# PCB-CCU-IRISCTRL.net
KiCad netlist of a schematic drawn in EAGLE
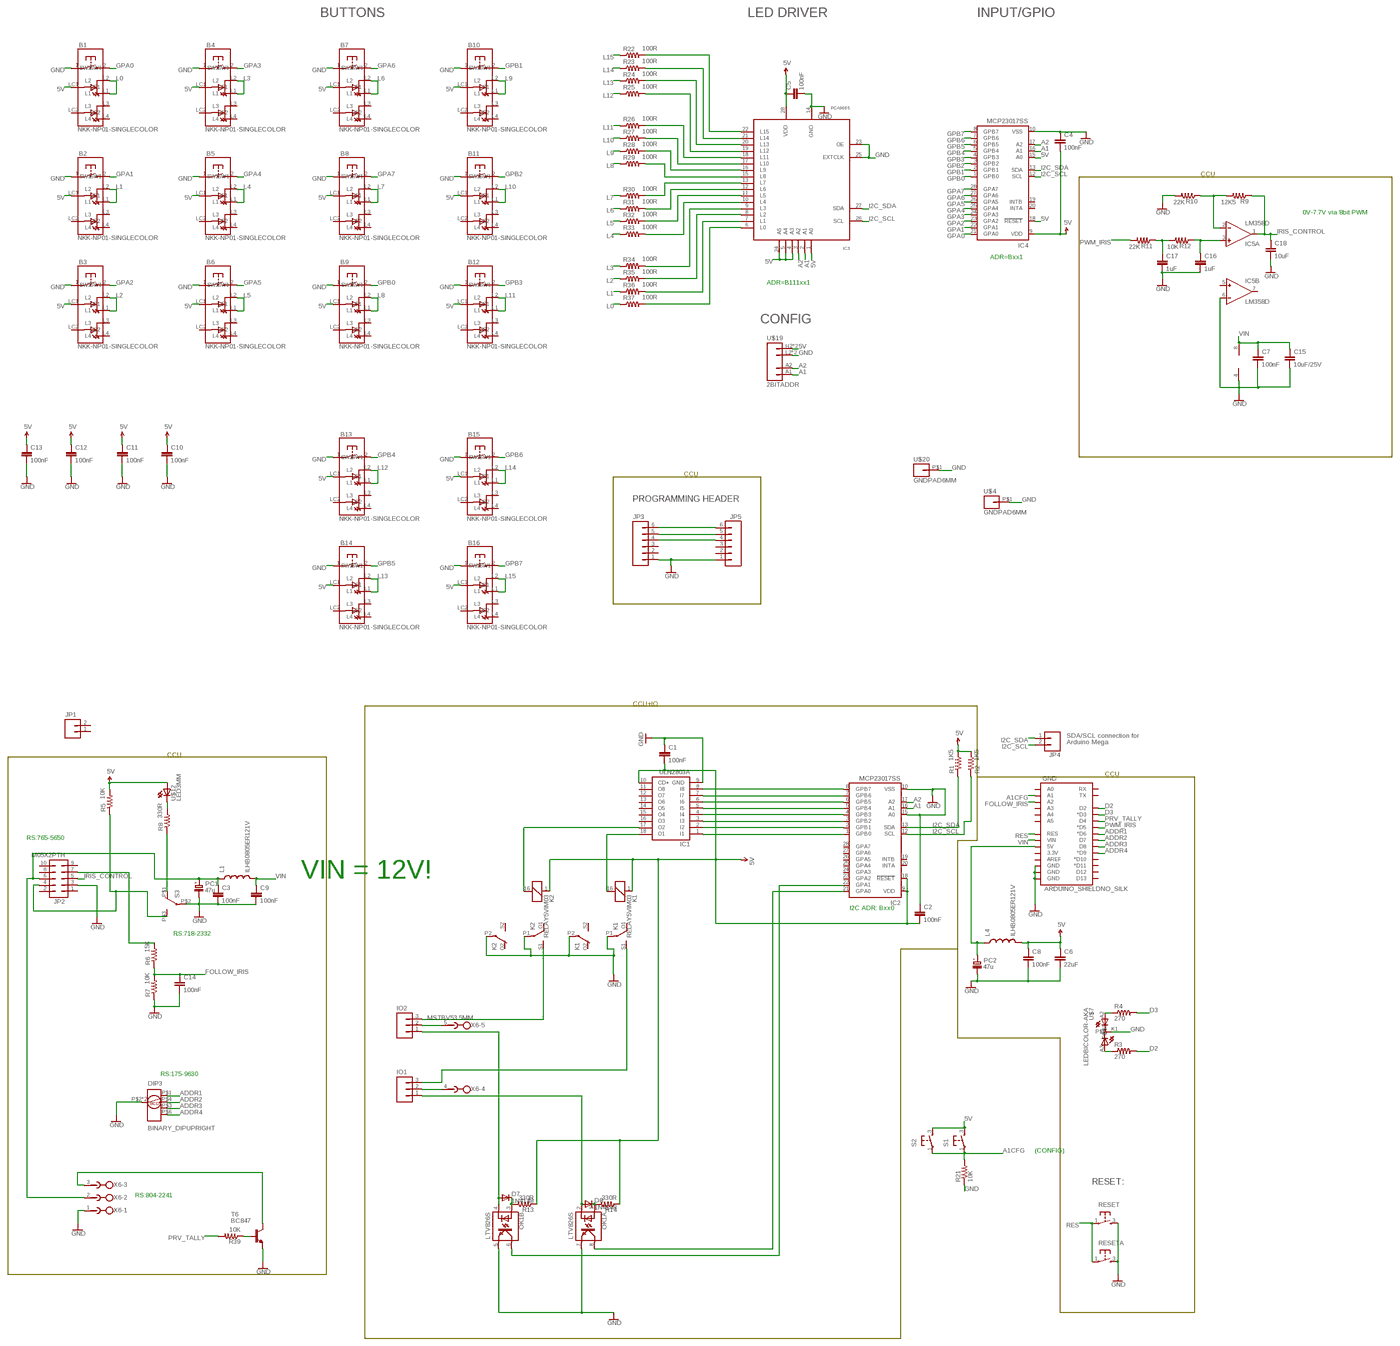
[diagram p0: schematic, sheet 1, overview]
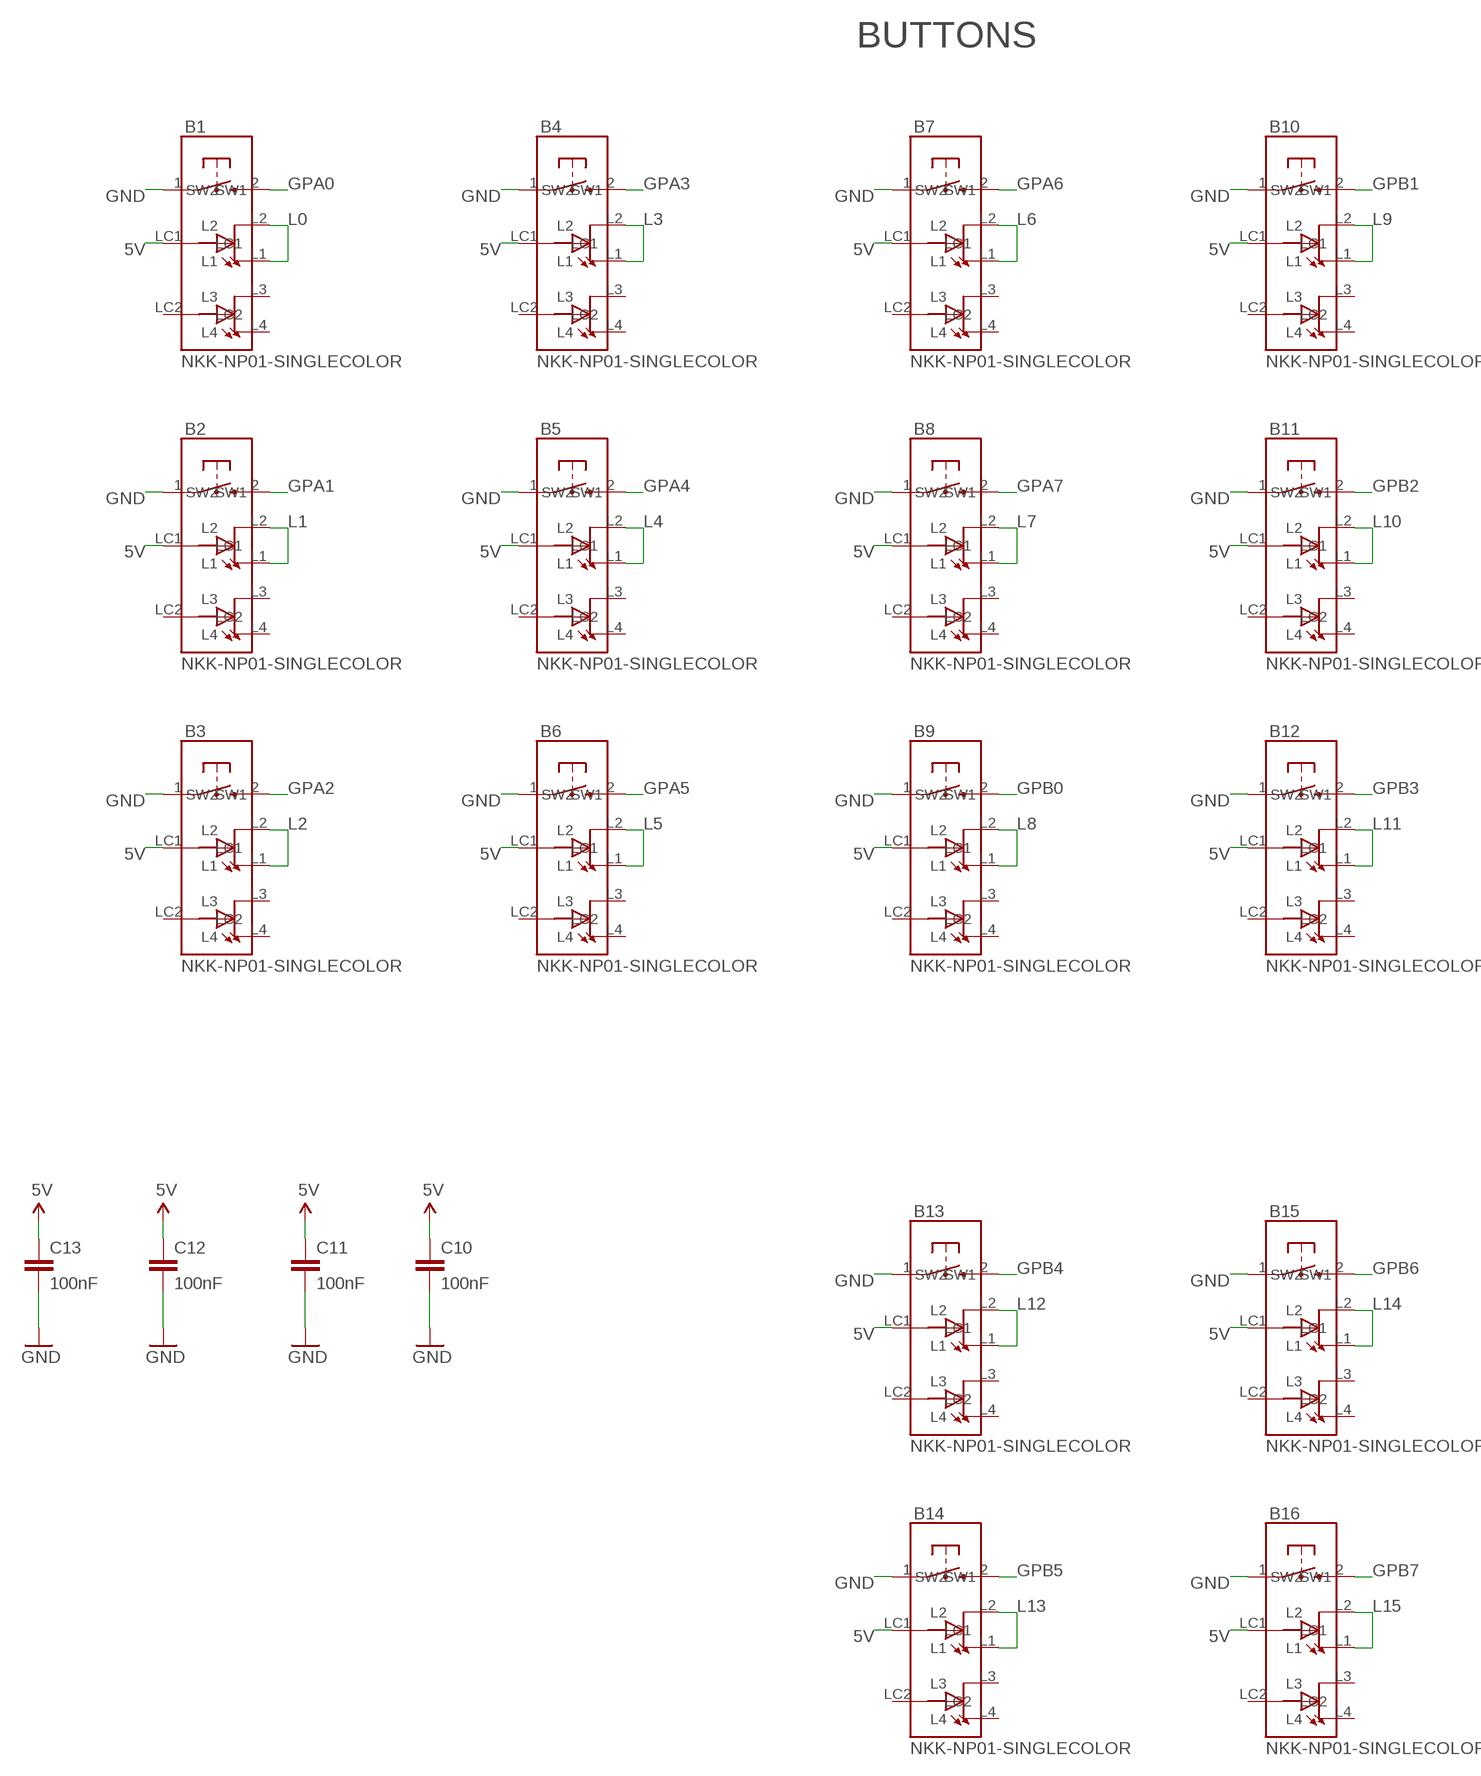
[diagram p1: schematic, sheet 1, part 1 of 4]
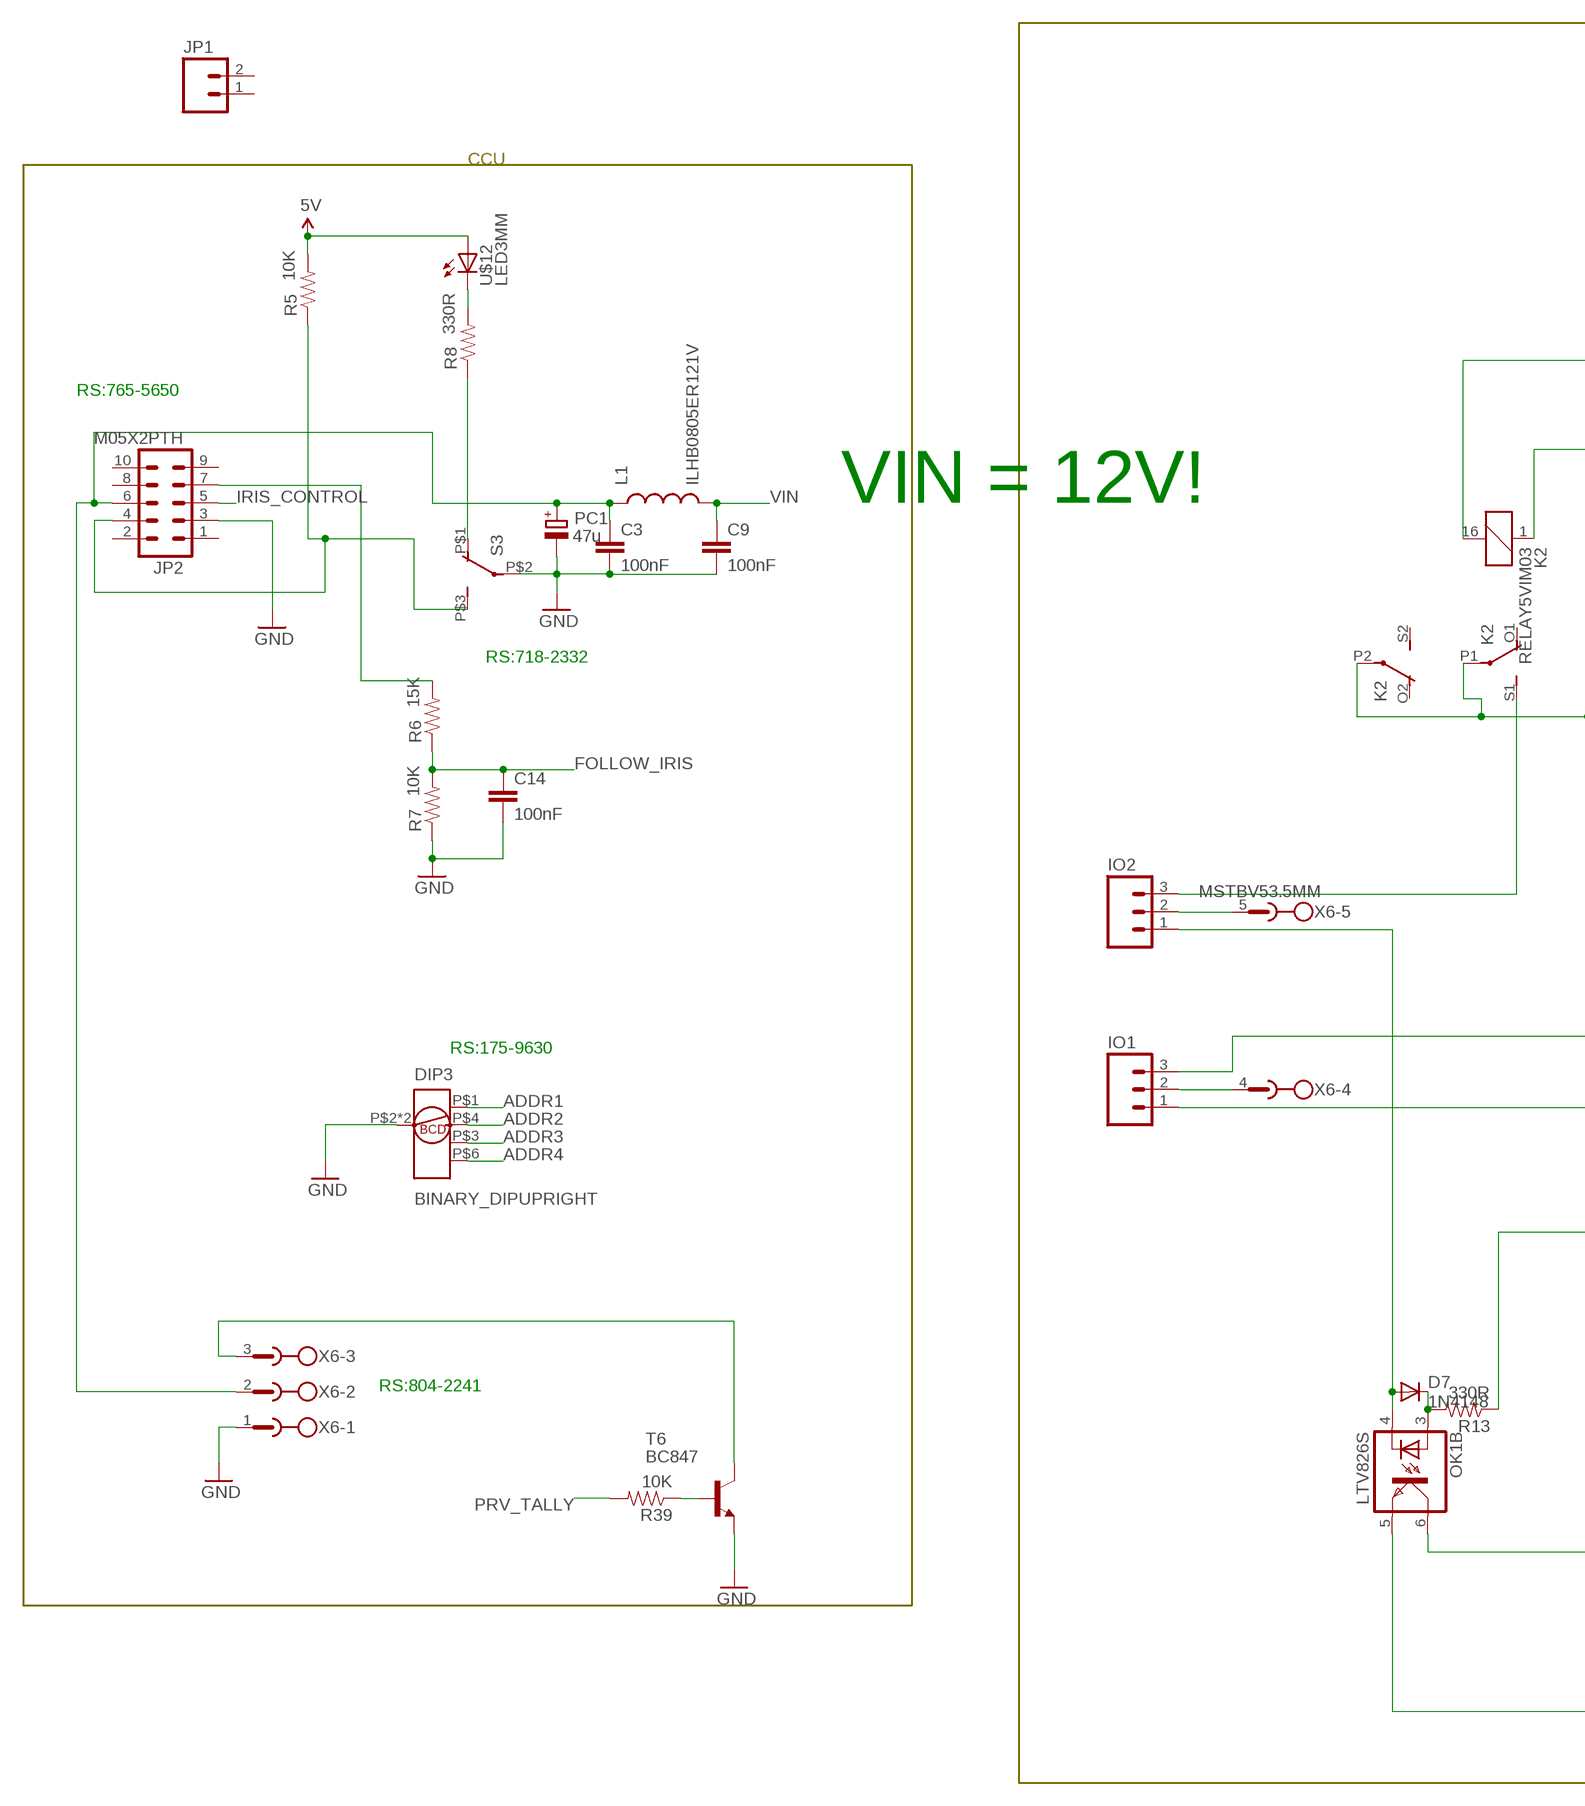
[diagram p2: schematic, sheet 1, part 2 of 4]
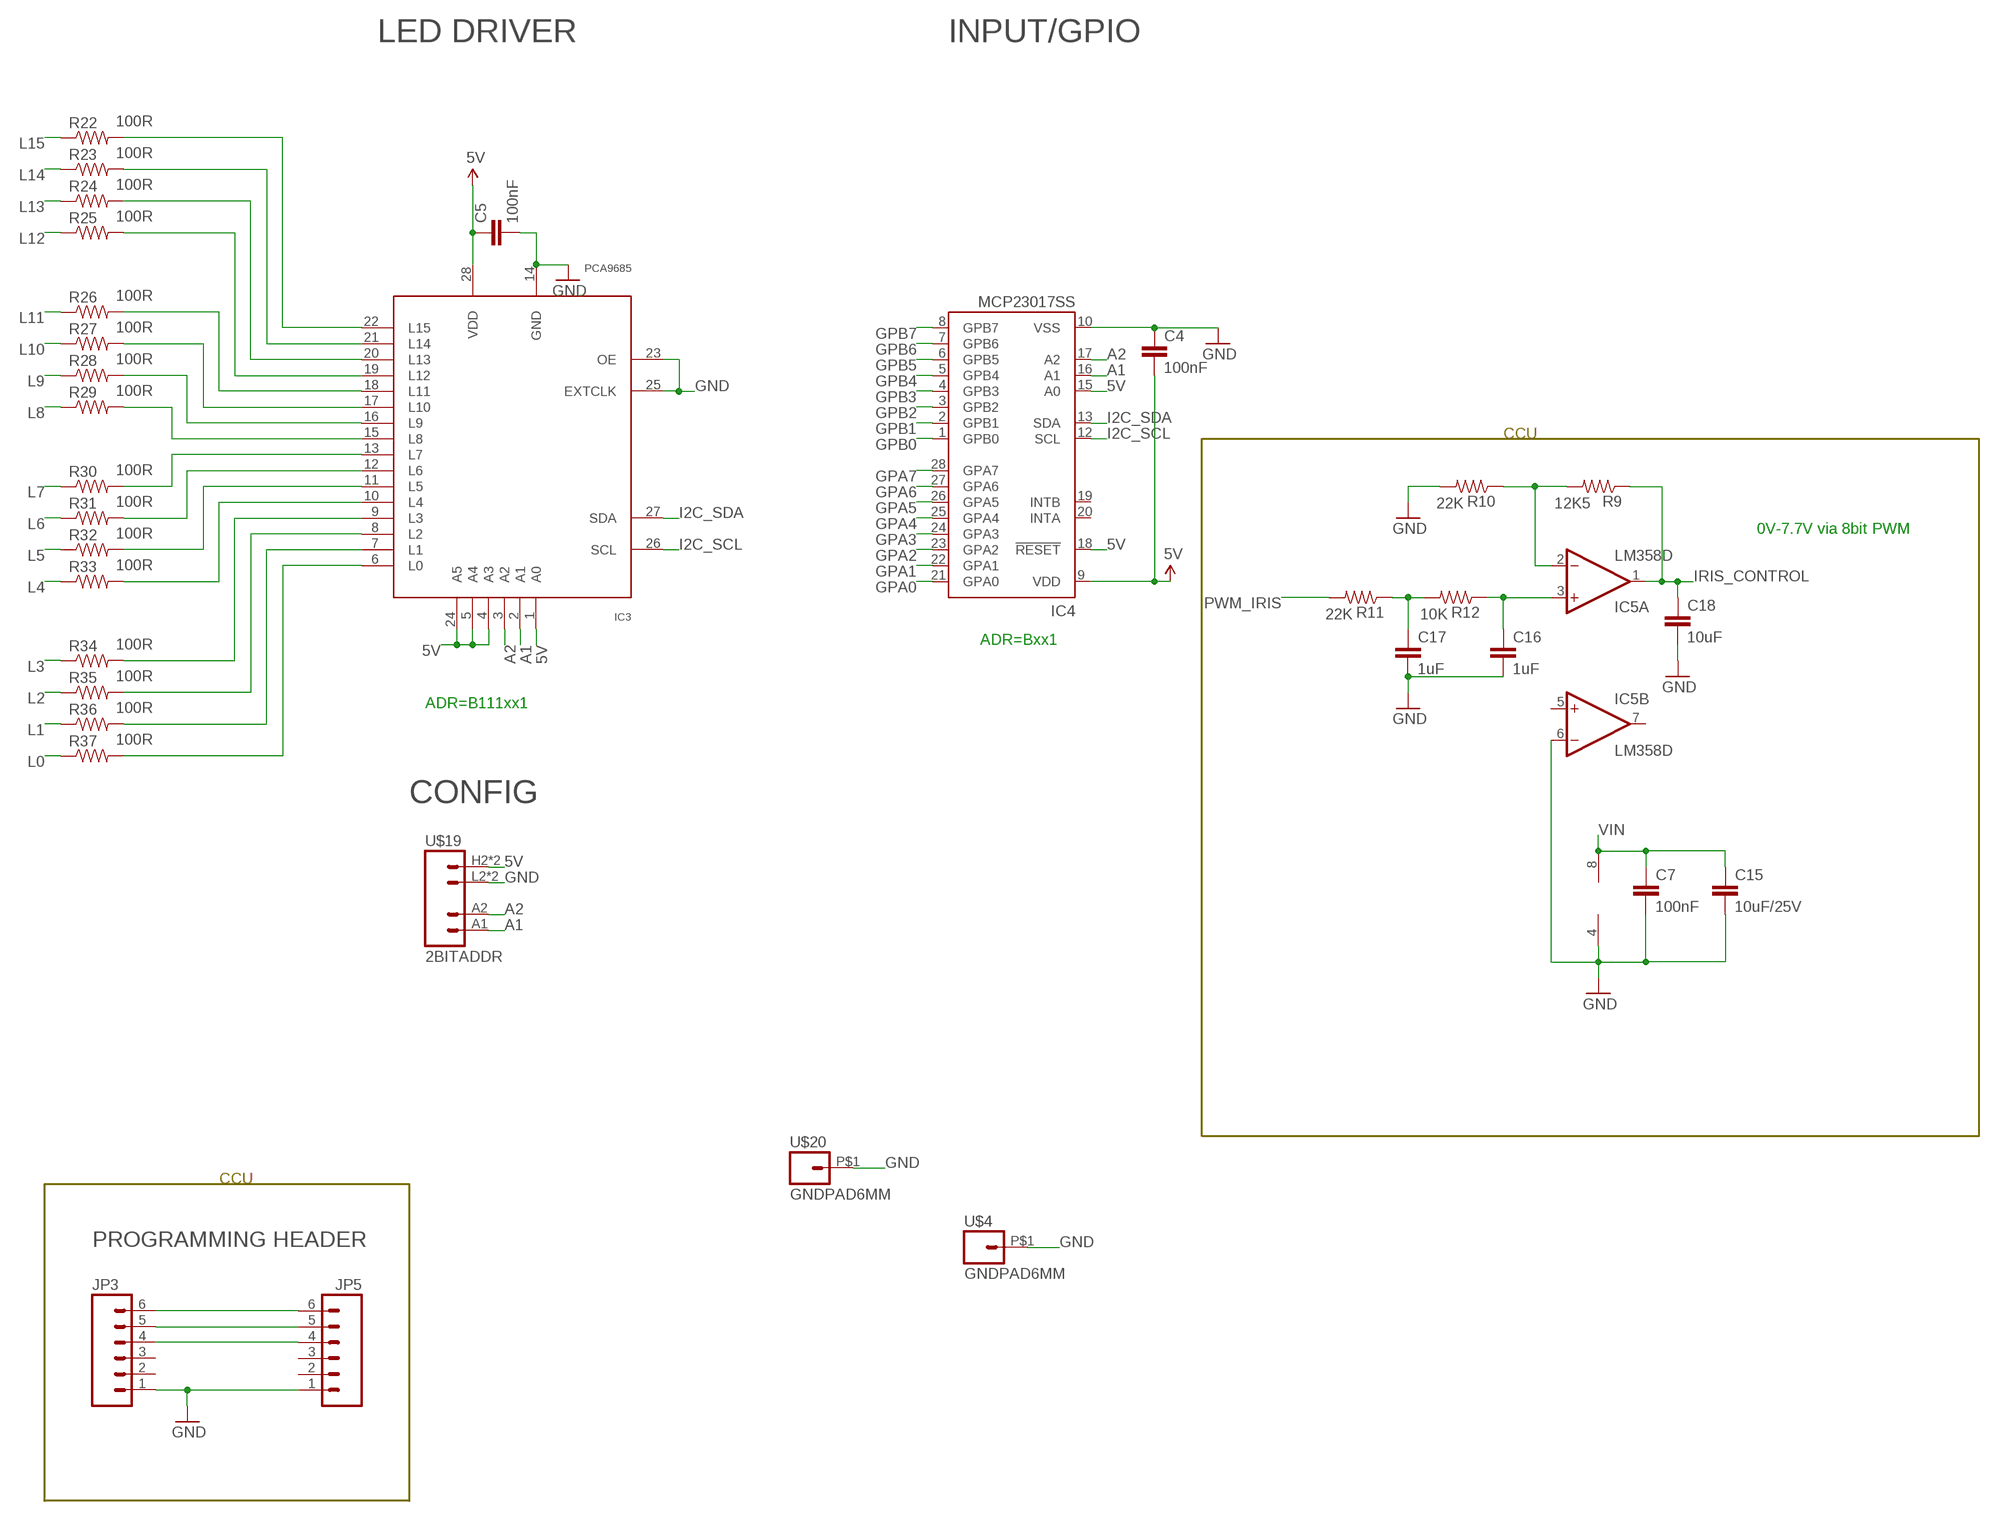
[diagram p3: schematic, sheet 1, part 3 of 4]
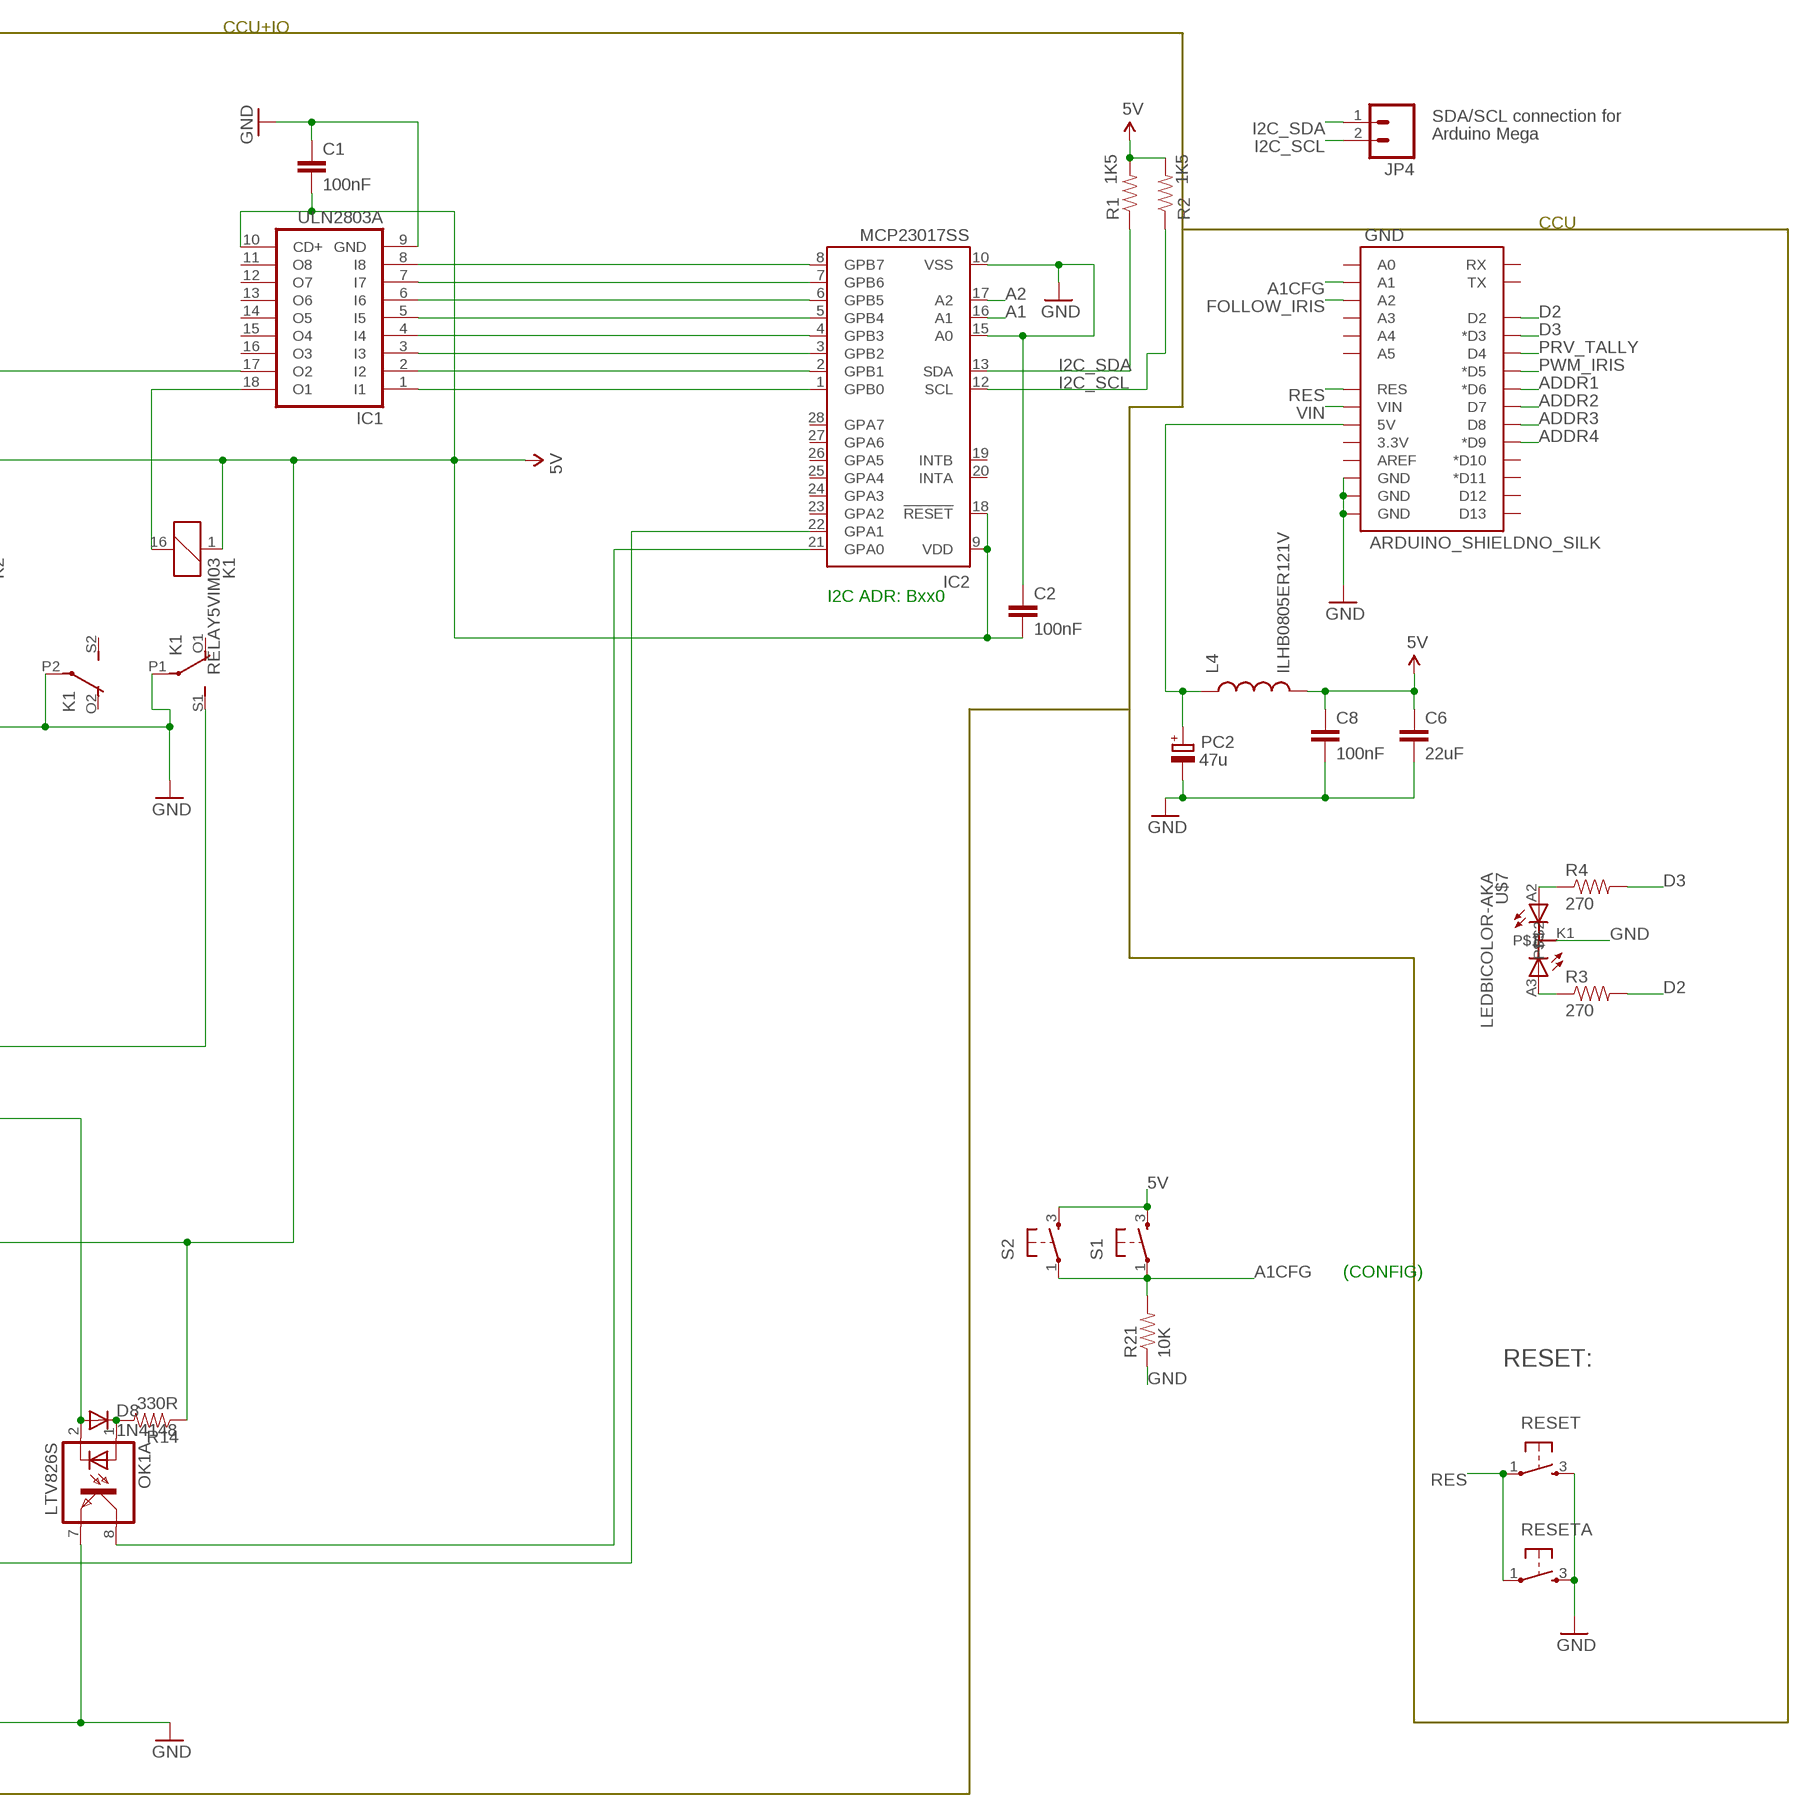
[diagram p4: schematic, sheet 1, part 4 of 4]

(export (version "E")
  (design (tool "Eeschema 10.0.6"))
  (components
    (comp (ref "B1")
      (value "NKK-NP01-SINGLECOLOR")
      (footprint "eagle-import:NKK-NP01")
      (libsource (lib "eagle-import") (part "NKK-NP01-SINGLECOLOR"))
    )
    (comp (ref "B2")
      (value "NKK-NP01-SINGLECOLOR")
      (footprint "eagle-import:NKK-NP01")
      (libsource (lib "eagle-import") (part "NKK-NP01-SINGLECOLOR"))
    )
    (comp (ref "B3")
      (value "NKK-NP01-SINGLECOLOR")
      (footprint "eagle-import:NKK-NP01")
      (libsource (lib "eagle-import") (part "NKK-NP01-SINGLECOLOR"))
    )
    (comp (ref "B4")
      (value "NKK-NP01-SINGLECOLOR")
      (footprint "eagle-import:NKK-NP01")
      (libsource (lib "eagle-import") (part "NKK-NP01-SINGLECOLOR"))
    )
    (comp (ref "B5")
      (value "NKK-NP01-SINGLECOLOR")
      (footprint "eagle-import:NKK-NP01")
      (libsource (lib "eagle-import") (part "NKK-NP01-SINGLECOLOR"))
    )
    (comp (ref "B6")
      (value "NKK-NP01-SINGLECOLOR")
      (footprint "eagle-import:NKK-NP01")
      (libsource (lib "eagle-import") (part "NKK-NP01-SINGLECOLOR"))
    )
    (comp (ref "B7")
      (value "NKK-NP01-SINGLECOLOR")
      (footprint "eagle-import:NKK-NP01")
      (libsource (lib "eagle-import") (part "NKK-NP01-SINGLECOLOR"))
    )
    (comp (ref "B8")
      (value "NKK-NP01-SINGLECOLOR")
      (footprint "eagle-import:NKK-NP01")
      (libsource (lib "eagle-import") (part "NKK-NP01-SINGLECOLOR"))
    )
    (comp (ref "B9")
      (value "NKK-NP01-SINGLECOLOR")
      (footprint "eagle-import:NKK-NP01")
      (libsource (lib "eagle-import") (part "NKK-NP01-SINGLECOLOR"))
    )
    (comp (ref "B10")
      (value "NKK-NP01-SINGLECOLOR")
      (footprint "eagle-import:NKK-NP01")
      (libsource (lib "eagle-import") (part "NKK-NP01-SINGLECOLOR"))
    )
    (comp (ref "B11")
      (value "NKK-NP01-SINGLECOLOR")
      (footprint "eagle-import:NKK-NP01")
      (libsource (lib "eagle-import") (part "NKK-NP01-SINGLECOLOR"))
    )
    (comp (ref "B12")
      (value "NKK-NP01-SINGLECOLOR")
      (footprint "eagle-import:NKK-NP01")
      (libsource (lib "eagle-import") (part "NKK-NP01-SINGLECOLOR"))
    )
    (comp (ref "B13")
      (value "NKK-NP01-SINGLECOLOR")
      (footprint "eagle-import:NKK-NP01")
      (libsource (lib "eagle-import") (part "NKK-NP01-SINGLECOLOR"))
    )
    (comp (ref "B14")
      (value "NKK-NP01-SINGLECOLOR")
      (footprint "eagle-import:NKK-NP01")
      (libsource (lib "eagle-import") (part "NKK-NP01-SINGLECOLOR"))
    )
    (comp (ref "B15")
      (value "NKK-NP01-SINGLECOLOR")
      (footprint "eagle-import:NKK-NP01")
      (libsource (lib "eagle-import") (part "NKK-NP01-SINGLECOLOR"))
    )
    (comp (ref "B16")
      (value "NKK-NP01-SINGLECOLOR")
      (footprint "eagle-import:NKK-NP01")
      (libsource (lib "eagle-import") (part "NKK-NP01-SINGLECOLOR"))
    )
    (comp (ref "C1")
      (value "100nF")
      (footprint "eagle-import:0805")
      (libsource (lib "eagle-import") (part "CAP0805"))
    )
    (comp (ref "C2")
      (value "100nF")
      (footprint "eagle-import:0603-CAP")
      (libsource (lib "eagle-import") (part "CAP0603-CAP"))
    )
    (comp (ref "C3")
      (value "100nF")
      (footprint "eagle-import:0603-CAP")
      (libsource (lib "eagle-import") (part "CAP0603-CAP"))
    )
    (comp (ref "C4")
      (value "100nF")
      (footprint "eagle-import:0603-CAP")
      (libsource (lib "eagle-import") (part "CAP0603-CAP"))
    )
    (comp (ref "C5")
      (value "100nF")
      (footprint "eagle-import:0603-CAP")
      (libsource (lib "eagle-import") (part "CAP0603-CAP"))
    )
    (comp (ref "C6")
      (value "22uF")
      (footprint "eagle-import:0805")
      (libsource (lib "eagle-import") (part "CAP0805"))
    )
    (comp (ref "C7")
      (value "100nF")
      (footprint "eagle-import:0603-CAP")
      (libsource (lib "eagle-import") (part "CAP0603-CAP"))
    )
    (comp (ref "C8")
      (value "100nF")
      (footprint "eagle-import:0603-CAP")
      (libsource (lib "eagle-import") (part "CAP0603-CAP"))
    )
    (comp (ref "C9")
      (value "100nF")
      (footprint "eagle-import:0603-CAP")
      (libsource (lib "eagle-import") (part "CAP0603-CAP"))
    )
    (comp (ref "C10")
      (value "100nF")
      (footprint "eagle-import:0603-CAP")
      (libsource (lib "eagle-import") (part "CAP0603-CAP"))
    )
    (comp (ref "C11")
      (value "100nF")
      (footprint "eagle-import:0603-CAP")
      (libsource (lib "eagle-import") (part "CAP0603-CAP"))
    )
    (comp (ref "C12")
      (value "100nF")
      (footprint "eagle-import:0603-CAP")
      (libsource (lib "eagle-import") (part "CAP0603-CAP"))
    )
    (comp (ref "C13")
      (value "100nF")
      (footprint "eagle-import:0603-CAP")
      (libsource (lib "eagle-import") (part "CAP0603-CAP"))
    )
    (comp (ref "C14")
      (value "100nF")
      (footprint "eagle-import:0603-CAP")
      (libsource (lib "eagle-import") (part "CAP0603-CAP"))
    )
    (comp (ref "C15")
      (value "10uF/25V")
      (footprint "eagle-import:0805")
      (libsource (lib "eagle-import") (part "CAP0805"))
    )
    (comp (ref "C16")
      (value "1uF")
      (footprint "eagle-import:0805")
      (libsource (lib "eagle-import") (part "CAP0805"))
    )
    (comp (ref "C17")
      (value "1uF")
      (footprint "eagle-import:0805")
      (libsource (lib "eagle-import") (part "CAP0805"))
    )
    (comp (ref "C18")
      (value "10uF")
      (footprint "eagle-import:0805")
      (libsource (lib "eagle-import") (part "CAP0805"))
    )
    (comp (ref "D7")
      (value "1N4148")
      (footprint "eagle-import:SOD-323")
      (libsource (lib "eagle-import") (part "DIODESOD"))
    )
    (comp (ref "D8")
      (value "1N4148")
      (footprint "eagle-import:SOD-323")
      (libsource (lib "eagle-import") (part "DIODESOD"))
    )
    (comp (ref "DIP3")
      (value "BINARY_DIPUPRIGHT")
      (footprint "eagle-import:P65SMT_UPRIGHT_TH")
      (libsource (lib "eagle-import") (part "BINARY_DIPUPRIGHT"))
    )
    (comp (ref "GND")
      (value "ARDUINO_SHIELDNO_SILK")
      (footprint "eagle-import:DUEMILANOVE_VIAS")
      (libsource (lib "eagle-import") (part "ARDUINO_SHIELDNO_SILK"))
    )
    (comp (ref "IC1")
      (value "ULN2803A")
      (footprint "eagle-import:SO18W")
      (libsource (lib "eagle-import") (part "ULN2803ASO18W"))
    )
    (comp (ref "IC2")
      (value "MCP23017SS")
      (footprint "eagle-import:SSOP28")
      (fields (field (name "MF") "MICROCHIP") (field (name "MPN") "MCP23017-E/SS"))
      (libsource (lib "eagle-import") (part "MCP23017SS"))
    )
    (comp (ref "IC3")
      (value "PCA9685")
      (footprint "eagle-import:TSSOP28")
      (libsource (lib "eagle-import") (part "PCA9685"))
    )
    (comp (ref "IC4")
      (value "MCP23017SS")
      (footprint "eagle-import:SSOP28")
      (fields
        (field (name "MF") "MICROCHIP")
        (field (name "MPN") "MCP23017-E/SS")
        (field (name "MPN_1") "MCP23017-E/SS")
        (field (name "OC_FARNELL") "1467674")
        (field (name "OC_NEWARK") "31K2960")
      )
      (libsource (lib "eagle-import") (part "MCP23017SS"))
    )
    (comp (ref "IC5")
      (value "LM358D")
      (footprint "eagle-import:SO08")
      (libsource (lib "eagle-import") (part "LM358D"))
    )
    (comp (ref "IO1")
      (value "M03LOCK")
      (footprint "eagle-import:1X03_LOCK")
      (libsource (lib "eagle-import") (part "M03LOCK"))
    )
    (comp (ref "IO2")
      (value "M03LOCK")
      (footprint "eagle-import:1X03_LOCK")
      (libsource (lib "eagle-import") (part "M03LOCK"))
    )
    (comp (ref "JP1")
      (value "M02PTH")
      (footprint "eagle-import:1X02")
      (libsource (lib "eagle-import") (part "M02PTH"))
    )
    (comp (ref "JP2")
      (value "M05X2PTH")
      (footprint "eagle-import:AVR_ICSP")
      (libsource (lib "eagle-import") (part "M05X2PTH"))
    )
    (comp (ref "JP3")
      (value "M06POLAR")
      (footprint "eagle-import:MOLEX-1X6")
      (libsource (lib "eagle-import") (part "M06POLAR"))
    )
    (comp (ref "JP4")
      (value "M02PTH")
      (footprint "eagle-import:1X02")
      (libsource (lib "eagle-import") (part "M02PTH"))
    )
    (comp (ref "JP5")
      (value "M06POLAR")
      (footprint "eagle-import:MOLEX-1X6")
      (libsource (lib "eagle-import") (part "M06POLAR"))
    )
    (comp (ref "K1")
      (value "RELAY5VIM03")
      (footprint "eagle-import:DS2Y")
      (libsource (lib "eagle-import") (part "RELAY5VIM03"))
    )
    (comp (ref "K2")
      (value "RELAY5VIM03")
      (footprint "eagle-import:DS2Y")
      (libsource (lib "eagle-import") (part "RELAY5VIM03"))
    )
    (comp (ref "L1")
      (value "ILHB0805ER121V")
      (footprint "eagle-import:0805")
      (libsource (lib "eagle-import") (part "INDUCTOR0805"))
    )
    (comp (ref "L4")
      (value "ILHB0805ER121V")
      (footprint "eagle-import:0805")
      (libsource (lib "eagle-import") (part "INDUCTOR0805"))
    )
    (comp (ref "OK1")
      (value "LTV826S")
      (footprint "eagle-import:DIL8-SMD")
      (libsource (lib "eagle-import") (part "LTV826S"))
    )
    (comp (ref "PC1")
      (value "47u")
      (footprint "eagle-import:PANASONIC_D")
      (libsource (lib "eagle-import") (part "CPOL-EUD"))
    )
    (comp (ref "PC2")
      (value "47u")
      (footprint "eagle-import:PANASONIC_D")
      (libsource (lib "eagle-import") (part "CPOL-EUD"))
    )
    (comp (ref "R1")
      (value "1K5")
      (footprint "eagle-import:0603-RES")
      (libsource (lib "eagle-import") (part "RESISTOR0603-RES"))
    )
    (comp (ref "R2")
      (value "1K5")
      (footprint "eagle-import:0603-RES")
      (libsource (lib "eagle-import") (part "RESISTOR0603-RES"))
    )
    (comp (ref "R3")
      (value "270")
      (footprint "eagle-import:0603-RES")
      (libsource (lib "eagle-import") (part "RESISTOR0603-RES"))
    )
    (comp (ref "R4")
      (value "270")
      (footprint "eagle-import:0603-RES")
      (libsource (lib "eagle-import") (part "RESISTOR0603-RES"))
    )
    (comp (ref "R5")
      (value "10K")
      (footprint "eagle-import:0603-RES")
      (libsource (lib "eagle-import") (part "RESISTOR0603-RES"))
    )
    (comp (ref "R6")
      (value "15K")
      (footprint "eagle-import:0603-RES")
      (libsource (lib "eagle-import") (part "RESISTOR0603-RES"))
    )
    (comp (ref "R7")
      (value "10K")
      (footprint "eagle-import:0603-RES")
      (libsource (lib "eagle-import") (part "RESISTOR0603-RES"))
    )
    (comp (ref "R8")
      (value "330R")
      (footprint "eagle-import:0603-RES")
      (libsource (lib "eagle-import") (part "RESISTOR0603-RES"))
    )
    (comp (ref "R9")
      (value "12K5")
      (footprint "eagle-import:0603-RES")
      (libsource (lib "eagle-import") (part "RESISTOR0603-RES"))
    )
    (comp (ref "R10")
      (value "22K")
      (footprint "eagle-import:0603-RES")
      (libsource (lib "eagle-import") (part "RESISTOR0603-RES"))
    )
    (comp (ref "R11")
      (value "22K")
      (footprint "eagle-import:0603-RES")
      (libsource (lib "eagle-import") (part "RESISTOR0603-RES"))
    )
    (comp (ref "R12")
      (value "10K")
      (footprint "eagle-import:0603-RES")
      (libsource (lib "eagle-import") (part "RESISTOR0603-RES"))
    )
    (comp (ref "R13")
      (value "330R")
      (footprint "eagle-import:0603-RES")
      (libsource (lib "eagle-import") (part "RESISTOR0603-RES"))
    )
    (comp (ref "R14")
      (value "330R")
      (footprint "eagle-import:0603-RES")
      (libsource (lib "eagle-import") (part "RESISTOR0603-RES"))
    )
    (comp (ref "R21")
      (value "10K")
      (footprint "eagle-import:0603-RES")
      (libsource (lib "eagle-import") (part "RESISTOR0603-RES"))
    )
    (comp (ref "R22")
      (value "100R")
      (footprint "eagle-import:0603-RES")
      (libsource (lib "eagle-import") (part "RESISTOR0603-RES"))
    )
    (comp (ref "R23")
      (value "100R")
      (footprint "eagle-import:0603-RES")
      (libsource (lib "eagle-import") (part "RESISTOR0603-RES"))
    )
    (comp (ref "R24")
      (value "100R")
      (footprint "eagle-import:0603-RES")
      (libsource (lib "eagle-import") (part "RESISTOR0603-RES"))
    )
    (comp (ref "R25")
      (value "100R")
      (footprint "eagle-import:0603-RES")
      (libsource (lib "eagle-import") (part "RESISTOR0603-RES"))
    )
    (comp (ref "R26")
      (value "100R")
      (footprint "eagle-import:0603-RES")
      (libsource (lib "eagle-import") (part "RESISTOR0603-RES"))
    )
    (comp (ref "R27")
      (value "100R")
      (footprint "eagle-import:0603-RES")
      (libsource (lib "eagle-import") (part "RESISTOR0603-RES"))
    )
    (comp (ref "R28")
      (value "100R")
      (footprint "eagle-import:0603-RES")
      (libsource (lib "eagle-import") (part "RESISTOR0603-RES"))
    )
    (comp (ref "R29")
      (value "100R")
      (footprint "eagle-import:0603-RES")
      (libsource (lib "eagle-import") (part "RESISTOR0603-RES"))
    )
    (comp (ref "R30")
      (value "100R")
      (footprint "eagle-import:0603-RES")
      (libsource (lib "eagle-import") (part "RESISTOR0603-RES"))
    )
    (comp (ref "R31")
      (value "100R")
      (footprint "eagle-import:0603-RES")
      (libsource (lib "eagle-import") (part "RESISTOR0603-RES"))
    )
    (comp (ref "R32")
      (value "100R")
      (footprint "eagle-import:0603-RES")
      (libsource (lib "eagle-import") (part "RESISTOR0603-RES"))
    )
    (comp (ref "R33")
      (value "100R")
      (footprint "eagle-import:0603-RES")
      (libsource (lib "eagle-import") (part "RESISTOR0603-RES"))
    )
    (comp (ref "R34")
      (value "100R")
      (footprint "eagle-import:0603-RES")
      (libsource (lib "eagle-import") (part "RESISTOR0603-RES"))
    )
    (comp (ref "R35")
      (value "100R")
      (footprint "eagle-import:0603-RES")
      (libsource (lib "eagle-import") (part "RESISTOR0603-RES"))
    )
    (comp (ref "R36")
      (value "100R")
      (footprint "eagle-import:0603-RES")
      (libsource (lib "eagle-import") (part "RESISTOR0603-RES"))
    )
    (comp (ref "R37")
      (value "100R")
      (footprint "eagle-import:0603-RES")
      (libsource (lib "eagle-import") (part "RESISTOR0603-RES"))
    )
    (comp (ref "R39")
      (value "10K")
      (footprint "eagle-import:0603-RES")
      (libsource (lib "eagle-import") (part "RESISTOR0603-RES"))
    )
    (comp (ref "RESET")
      (value "TAC_SWITCH")
      (footprint "eagle-import:PUSHBUTTON")
      (libsource (lib "eagle-import") (part "TAC_SWITCH"))
    )
    (comp (ref "RESETA")
      (value "TAC_SWITCH")
      (footprint "eagle-import:PUSHBUTTON")
      (libsource (lib "eagle-import") (part "TAC_SWITCH"))
    )
    (comp (ref "S1")
      (value "TAC_SWITCH")
      (footprint "eagle-import:PUSHBUTTON")
      (libsource (lib "eagle-import") (part "TAC_SWITCH"))
    )
    (comp (ref "S2")
      (value "TAC_SWITCH")
      (footprint "eagle-import:PUSHBUTTON")
      (libsource (lib "eagle-import") (part "TAC_SWITCH"))
    )
    (comp (ref "S3")
      (value "SWITCH-DPST")
      (footprint "eagle-import:TECONNECTIVITY-DPST")
      (libsource (lib "eagle-import") (part "SWITCH-DPST"))
    )
    (comp (ref "T6")
      (value "BC847")
      (footprint "eagle-import:SOT23")
      (libsource (lib "eagle-import") (part "BC847"))
    )
    (comp (ref "U$4")
      (value "GNDPAD6MM")
      (footprint "eagle-import:3.2MMPAD6MM")
      (libsource (lib "eagle-import") (part "GNDPAD6MM"))
    )
    (comp (ref "U$7")
      (value "LEDBICOLOR-AKA")
      (footprint "eagle-import:LED5MM-BICOLOR")
      (libsource (lib "eagle-import") (part "LEDBICOLOR-AKA"))
    )
    (comp (ref "U$12")
      (value "LED3MM")
      (footprint "eagle-import:LED3MM")
      (libsource (lib "eagle-import") (part "LED3MM"))
    )
    (comp (ref "U$19")
      (value "2BITADDR")
      (footprint "eagle-import:2BITADDR")
      (libsource (lib "eagle-import") (part "2BITADDR"))
    )
    (comp (ref "U$20")
      (value "GNDPAD6MM")
      (footprint "eagle-import:3.2MMPAD6MM")
      (libsource (lib "eagle-import") (part "GNDPAD6MM"))
    )
    (comp (ref "X6")
      (value "MSTBV53.5MM")
      (footprint "eagle-import:MSTBV5-3.5")
      (libsource (lib "eagle-import") (part "MSTBV53.5MM"))
    )
  )
  (nets
    (net (code "1") (name "5V") (class "Default")
      (node (ref "B1") (pin "LC1") (pinfunction "LC1_LC1") (pintype "bidirectional"))
      (node (ref "B10") (pin "LC1") (pinfunction "LC1_LC1") (pintype "bidirectional"))
      (node (ref "B11") (pin "LC1") (pinfunction "LC1_LC1") (pintype "bidirectional"))
      (node (ref "B12") (pin "LC1") (pinfunction "LC1_LC1") (pintype "bidirectional"))
      (node (ref "B13") (pin "LC1") (pinfunction "LC1_LC1") (pintype "bidirectional"))
      (node (ref "B14") (pin "LC1") (pinfunction "LC1_LC1") (pintype "bidirectional"))
      (node (ref "B15") (pin "LC1") (pinfunction "LC1_LC1") (pintype "bidirectional"))
      (node (ref "B16") (pin "LC1") (pinfunction "LC1_LC1") (pintype "bidirectional"))
      (node (ref "B2") (pin "LC1") (pinfunction "LC1_LC1") (pintype "bidirectional"))
      (node (ref "B3") (pin "LC1") (pinfunction "LC1_LC1") (pintype "bidirectional"))
      (node (ref "B4") (pin "LC1") (pinfunction "LC1_LC1") (pintype "bidirectional"))
      (node (ref "B5") (pin "LC1") (pinfunction "LC1_LC1") (pintype "bidirectional"))
      (node (ref "B6") (pin "LC1") (pinfunction "LC1_LC1") (pintype "bidirectional"))
      (node (ref "B7") (pin "LC1") (pinfunction "LC1_LC1") (pintype "bidirectional"))
      (node (ref "B8") (pin "LC1") (pinfunction "LC1_LC1") (pintype "bidirectional"))
      (node (ref "B9") (pin "LC1") (pinfunction "LC1_LC1") (pintype "bidirectional"))
      (node (ref "C1") (pin "2") (pinfunction "2_2") (pintype "passive"))
      (node (ref "C10") (pin "1") (pinfunction "1_1") (pintype "passive"))
      (node (ref "C11") (pin "1") (pinfunction "1_1") (pintype "passive"))
      (node (ref "C12") (pin "1") (pinfunction "1_1") (pintype "passive"))
      (node (ref "C13") (pin "1") (pinfunction "1_1") (pintype "passive"))
      (node (ref "C2") (pin "2") (pinfunction "2_2") (pintype "passive"))
      (node (ref "C4") (pin "2") (pinfunction "2_2") (pintype "passive"))
      (node (ref "C5") (pin "1") (pinfunction "1_1") (pintype "passive"))
      (node (ref "C6") (pin "1") (pinfunction "1_1") (pintype "passive"))
      (node (ref "C8") (pin "1") (pinfunction "1_1") (pintype "passive"))
      (node (ref "IC1") (pin "10") (pinfunction "CD+_10") (pintype "passive"))
      (node (ref "IC2") (pin "18") (pinfunction "~{RESET}_18") (pintype "input"))
      (node (ref "IC2") (pin "9") (pinfunction "VDD_9") (pintype "power_in"))
      (node (ref "IC3") (pin "1") (pinfunction "A0_1") (pintype "input"))
      (node (ref "IC3") (pin "24") (pinfunction "A5_24") (pintype "input"))
      (node (ref "IC3") (pin "28") (pinfunction "VDD_28") (pintype "power_in"))
      (node (ref "IC3") (pin "4") (pinfunction "A3_4") (pintype "input"))
      (node (ref "IC3") (pin "5") (pinfunction "A4_5") (pintype "input"))
      (node (ref "IC4") (pin "15") (pinfunction "A0_15") (pintype "input"))
      (node (ref "IC4") (pin "18") (pinfunction "~{RESET}_18") (pintype "input"))
      (node (ref "IC4") (pin "9") (pinfunction "VDD_9") (pintype "power_in"))
      (node (ref "K1") (pin "1") (pinfunction "1_1") (pintype "passive"))
      (node (ref "K2") (pin "1") (pinfunction "1_1") (pintype "passive"))
      (node (ref "L4") (pin "2") (pinfunction "2_2") (pintype "passive"))
      (node (ref "R1") (pin "2") (pinfunction "2_2") (pintype "passive"))
      (node (ref "R13") (pin "1") (pinfunction "1_1") (pintype "passive"))
      (node (ref "R14") (pin "1") (pinfunction "1_1") (pintype "passive"))
      (node (ref "R2") (pin "2") (pinfunction "2_2") (pintype "passive"))
      (node (ref "R5") (pin "2") (pinfunction "2_2") (pintype "passive"))
      (node (ref "S1") (pin "3") (pinfunction "3_3") (pintype "passive"))
      (node (ref "S2") (pin "3") (pinfunction "3_3") (pintype "passive"))
      (node (ref "U$12") (pin "A") (pinfunction "A_A") (pintype "passive"))
      (node (ref "U$19") (pin "H2") (pinfunction "VCC_H2") (pintype "passive"))
      (node (ref "U$19") (pin "H3") (pinfunction "VCC_H3") (pintype "passive"))
    )
    (net (code "2") (name "A1") (class "Default")
      (node (ref "IC2") (pin "16") (pinfunction "A1_16") (pintype "input"))
      (node (ref "IC3") (pin "2") (pinfunction "A1_2") (pintype "input"))
      (node (ref "IC4") (pin "16") (pinfunction "A1_16") (pintype "input"))
      (node (ref "U$19") (pin "A1") (pinfunction "A1_A1") (pintype "passive"))
    )
    (net (code "3") (name "A1CFG") (class "Default")
      (node (ref "GND") (pin "A1") (pinfunction "A1_A1") (pintype "bidirectional"))
      (node (ref "R21") (pin "2") (pinfunction "2_2") (pintype "passive"))
      (node (ref "S1") (pin "1") (pinfunction "1_1") (pintype "passive"))
      (node (ref "S2") (pin "1") (pinfunction "1_1") (pintype "passive"))
    )
    (net (code "4") (name "A2") (class "Default")
      (node (ref "IC2") (pin "17") (pinfunction "A2_17") (pintype "input"))
      (node (ref "IC3") (pin "3") (pinfunction "A2_3") (pintype "input"))
      (node (ref "IC4") (pin "17") (pinfunction "A2_17") (pintype "input"))
      (node (ref "U$19") (pin "A2") (pinfunction "A2_A2") (pintype "passive"))
    )
    (net (code "5") (name "ADDR1") (class "Default")
      (node (ref "DIP3") (pin "P$1") (pinfunction "1_P$1") (pintype "passive"))
      (node (ref "GND") (pin "D6") (pinfunction "*D6_D6") (pintype "bidirectional"))
    )
    (net (code "6") (name "ADDR2") (class "Default")
      (node (ref "DIP3") (pin "P$4") (pinfunction "2_P$4") (pintype "passive"))
      (node (ref "GND") (pin "D7") (pinfunction "D7_D7") (pintype "bidirectional"))
    )
    (net (code "7") (name "ADDR3") (class "Default")
      (node (ref "DIP3") (pin "P$3") (pinfunction "4_P$3") (pintype "passive"))
      (node (ref "GND") (pin "D8") (pinfunction "D8_D8") (pintype "bidirectional"))
    )
    (net (code "8") (name "ADDR4") (class "Default")
      (node (ref "DIP3") (pin "P$6") (pinfunction "8_P$6") (pintype "passive"))
      (node (ref "GND") (pin "D9") (pinfunction "*D9_D9") (pintype "bidirectional"))
    )
    (net (code "9") (name "D2") (class "Default")
      (node (ref "GND") (pin "D2") (pinfunction "D2_D2") (pintype "bidirectional"))
      (node (ref "R3") (pin "2") (pinfunction "2_2") (pintype "passive"))
    )
    (net (code "10") (name "D3") (class "Default")
      (node (ref "GND") (pin "D3") (pinfunction "*D3_D3") (pintype "bidirectional"))
      (node (ref "R4") (pin "2") (pinfunction "2_2") (pintype "passive"))
    )
    (net (code "11") (name "FOLLOW_IRIS") (class "Default")
      (node (ref "C14") (pin "1") (pinfunction "1_1") (pintype "passive"))
      (node (ref "GND") (pin "A2") (pinfunction "A2_A2") (pintype "bidirectional"))
      (node (ref "R6") (pin "1") (pinfunction "1_1") (pintype "passive"))
      (node (ref "R7") (pin "2") (pinfunction "2_2") (pintype "passive"))
    )
    (net (code "12") (name "GND") (class "Default")
      (node (ref "B1") (pin "1") (pinfunction "SW1_1") (pintype "bidirectional"))
      (node (ref "B10") (pin "1") (pinfunction "SW1_1") (pintype "bidirectional"))
      (node (ref "B11") (pin "1") (pinfunction "SW1_1") (pintype "bidirectional"))
      (node (ref "B12") (pin "1") (pinfunction "SW1_1") (pintype "bidirectional"))
      (node (ref "B13") (pin "1") (pinfunction "SW1_1") (pintype "bidirectional"))
      (node (ref "B14") (pin "1") (pinfunction "SW1_1") (pintype "bidirectional"))
      (node (ref "B15") (pin "1") (pinfunction "SW1_1") (pintype "bidirectional"))
      (node (ref "B16") (pin "1") (pinfunction "SW1_1") (pintype "bidirectional"))
      (node (ref "B2") (pin "1") (pinfunction "SW1_1") (pintype "bidirectional"))
      (node (ref "B3") (pin "1") (pinfunction "SW1_1") (pintype "bidirectional"))
      (node (ref "B4") (pin "1") (pinfunction "SW1_1") (pintype "bidirectional"))
      (node (ref "B5") (pin "1") (pinfunction "SW1_1") (pintype "bidirectional"))
      (node (ref "B6") (pin "1") (pinfunction "SW1_1") (pintype "bidirectional"))
      (node (ref "B7") (pin "1") (pinfunction "SW1_1") (pintype "bidirectional"))
      (node (ref "B8") (pin "1") (pinfunction "SW1_1") (pintype "bidirectional"))
      (node (ref "B9") (pin "1") (pinfunction "SW1_1") (pintype "bidirectional"))
      (node (ref "C1") (pin "1") (pinfunction "1_1") (pintype "passive"))
      (node (ref "C10") (pin "2") (pinfunction "2_2") (pintype "passive"))
      (node (ref "C11") (pin "2") (pinfunction "2_2") (pintype "passive"))
      (node (ref "C12") (pin "2") (pinfunction "2_2") (pintype "passive"))
      (node (ref "C13") (pin "2") (pinfunction "2_2") (pintype "passive"))
      (node (ref "C14") (pin "2") (pinfunction "2_2") (pintype "passive"))
      (node (ref "C15") (pin "2") (pinfunction "2_2") (pintype "passive"))
      (node (ref "C16") (pin "2") (pinfunction "2_2") (pintype "passive"))
      (node (ref "C17") (pin "2") (pinfunction "2_2") (pintype "passive"))
      (node (ref "C18") (pin "2") (pinfunction "2_2") (pintype "passive"))
      (node (ref "C2") (pin "1") (pinfunction "1_1") (pintype "passive"))
      (node (ref "C3") (pin "2") (pinfunction "2_2") (pintype "passive"))
      (node (ref "C4") (pin "1") (pinfunction "1_1") (pintype "passive"))
      (node (ref "C5") (pin "2") (pinfunction "2_2") (pintype "passive"))
      (node (ref "C6") (pin "2") (pinfunction "2_2") (pintype "passive"))
      (node (ref "C7") (pin "2") (pinfunction "2_2") (pintype "passive"))
      (node (ref "C8") (pin "2") (pinfunction "2_2") (pintype "passive"))
      (node (ref "C9") (pin "2") (pinfunction "2_2") (pintype "passive"))
      (node (ref "DIP3") (pin "P$2") (pinfunction "GND_P$2") (pintype "passive"))
      (node (ref "DIP3") (pin "P$5") (pinfunction "GND_P$5") (pintype "passive"))
      (node (ref "GND") (pin "GND@0") (pinfunction "GND_GND@0") (pintype "bidirectional"))
      (node (ref "GND") (pin "GND@1") (pinfunction "GND_GND@1") (pintype "bidirectional"))
      (node (ref "GND") (pin "GND@2") (pinfunction "GND_GND@2") (pintype "bidirectional"))
      (node (ref "IC1") (pin "9") (pinfunction "GND_9") (pintype "power_in"))
      (node (ref "IC2") (pin "10") (pinfunction "VSS_10") (pintype "power_in"))
      (node (ref "IC2") (pin "15") (pinfunction "A0_15") (pintype "input"))
      (node (ref "IC3") (pin "14") (pinfunction "GND_14") (pintype "power_in"))
      (node (ref "IC3") (pin "23") (pinfunction "OE_23") (pintype "input"))
      (node (ref "IC3") (pin "25") (pinfunction "EXTCLK_25") (pintype "input"))
      (node (ref "IC4") (pin "10") (pinfunction "VSS_10") (pintype "power_in"))
      (node (ref "IC5") (pin "4") (pinfunction "V-_4") (pintype "power_in"))
      (node (ref "IC5") (pin "6") (pinfunction "-IN_6") (pintype "input"))
      (node (ref "JP2") (pin "3") (pinfunction "3_3") (pintype "passive"))
      (node (ref "JP3") (pin "1") (pinfunction "1_1") (pintype "passive"))
      (node (ref "JP5") (pin "1") (pinfunction "1_1") (pintype "passive"))
      (node (ref "K1") (pin "P1") (pinfunction "P_P1") (pintype "passive"))
      (node (ref "K1") (pin "P2") (pinfunction "P_P2") (pintype "passive"))
      (node (ref "K2") (pin "P1") (pinfunction "P_P1") (pintype "passive"))
      (node (ref "K2") (pin "P2") (pinfunction "P_P2") (pintype "passive"))
      (node (ref "OK1") (pin "5") (pinfunction "EMIT_5") (pintype "passive"))
      (node (ref "OK1") (pin "7") (pinfunction "EMIT_7") (pintype "passive"))
      (node (ref "PC1") (pin "-") (pinfunction "-_-") (pintype "passive"))
      (node (ref "PC2") (pin "-") (pinfunction "-_-") (pintype "passive"))
      (node (ref "R10") (pin "2") (pinfunction "2_2") (pintype "passive"))
      (node (ref "R21") (pin "1") (pinfunction "1_1") (pintype "passive"))
      (node (ref "R7") (pin "1") (pinfunction "1_1") (pintype "passive"))
      (node (ref "RESET") (pin "3") (pinfunction "3_3") (pintype "passive"))
      (node (ref "RESETA") (pin "3") (pinfunction "3_3") (pintype "passive"))
      (node (ref "S3") (pin "P$2") (pinfunction "P_P$2") (pintype "passive"))
      (node (ref "T6") (pin "2") (pinfunction "E_2") (pintype "passive"))
      (node (ref "U$19") (pin "L2") (pinfunction "GND_L2") (pintype "passive"))
      (node (ref "U$19") (pin "L3") (pinfunction "GND_L3") (pintype "passive"))
      (node (ref "U$20") (pin "P$1") (pinfunction "1_P$1") (pintype "passive"))
      (node (ref "U$4") (pin "P$1") (pinfunction "1_P$1") (pintype "passive"))
      (node (ref "U$7") (pin "K1") (pinfunction "P$1_K1") (pintype "bidirectional"))
      (node (ref "X6") (pin "1") (pinfunction "1_1") (pintype "passive"))
    )
    (net (code "13") (name "GPA0") (class "Default")
      (node (ref "B1") (pin "2") (pinfunction "SW2_2") (pintype "bidirectional"))
      (node (ref "IC4") (pin "21") (pinfunction "GPA0_21") (pintype "bidirectional"))
    )
    (net (code "14") (name "GPA1") (class "Default")
      (node (ref "B2") (pin "2") (pinfunction "SW2_2") (pintype "bidirectional"))
      (node (ref "IC4") (pin "22") (pinfunction "GPA1_22") (pintype "bidirectional"))
    )
    (net (code "15") (name "GPA2") (class "Default")
      (node (ref "B3") (pin "2") (pinfunction "SW2_2") (pintype "bidirectional"))
      (node (ref "IC4") (pin "23") (pinfunction "GPA2_23") (pintype "bidirectional"))
    )
    (net (code "16") (name "GPA3") (class "Default")
      (node (ref "B4") (pin "2") (pinfunction "SW2_2") (pintype "bidirectional"))
      (node (ref "IC4") (pin "24") (pinfunction "GPA3_24") (pintype "bidirectional"))
    )
    (net (code "17") (name "GPA4") (class "Default")
      (node (ref "B5") (pin "2") (pinfunction "SW2_2") (pintype "bidirectional"))
      (node (ref "IC4") (pin "25") (pinfunction "GPA4_25") (pintype "bidirectional"))
    )
    (net (code "18") (name "GPA5") (class "Default")
      (node (ref "B6") (pin "2") (pinfunction "SW2_2") (pintype "bidirectional"))
      (node (ref "IC4") (pin "26") (pinfunction "GPA5_26") (pintype "bidirectional"))
    )
    (net (code "19") (name "GPA6") (class "Default")
      (node (ref "B7") (pin "2") (pinfunction "SW2_2") (pintype "bidirectional"))
      (node (ref "IC4") (pin "27") (pinfunction "GPA6_27") (pintype "bidirectional"))
    )
    (net (code "20") (name "GPA7") (class "Default")
      (node (ref "B8") (pin "2") (pinfunction "SW2_2") (pintype "bidirectional"))
      (node (ref "IC4") (pin "28") (pinfunction "GPA7_28") (pintype "bidirectional"))
    )
    (net (code "21") (name "GPB0") (class "Default")
      (node (ref "B9") (pin "2") (pinfunction "SW2_2") (pintype "bidirectional"))
      (node (ref "IC4") (pin "1") (pinfunction "GPB0_1") (pintype "bidirectional"))
    )
    (net (code "22") (name "GPB1") (class "Default")
      (node (ref "B10") (pin "2") (pinfunction "SW2_2") (pintype "bidirectional"))
      (node (ref "IC4") (pin "2") (pinfunction "GPB1_2") (pintype "bidirectional"))
    )
    (net (code "23") (name "GPB2") (class "Default")
      (node (ref "B11") (pin "2") (pinfunction "SW2_2") (pintype "bidirectional"))
      (node (ref "IC4") (pin "3") (pinfunction "GPB2_3") (pintype "bidirectional"))
    )
    (net (code "24") (name "GPB3") (class "Default")
      (node (ref "B12") (pin "2") (pinfunction "SW2_2") (pintype "bidirectional"))
      (node (ref "IC4") (pin "4") (pinfunction "GPB3_4") (pintype "bidirectional"))
    )
    (net (code "25") (name "GPB4") (class "Default")
      (node (ref "B13") (pin "2") (pinfunction "SW2_2") (pintype "bidirectional"))
      (node (ref "IC4") (pin "5") (pinfunction "GPB4_5") (pintype "bidirectional"))
    )
    (net (code "26") (name "GPB5") (class "Default")
      (node (ref "B14") (pin "2") (pinfunction "SW2_2") (pintype "bidirectional"))
      (node (ref "IC4") (pin "6") (pinfunction "GPB5_6") (pintype "bidirectional"))
    )
    (net (code "27") (name "GPB6") (class "Default")
      (node (ref "B15") (pin "2") (pinfunction "SW2_2") (pintype "bidirectional"))
      (node (ref "IC4") (pin "7") (pinfunction "GPB6_7") (pintype "bidirectional"))
    )
    (net (code "28") (name "GPB7") (class "Default")
      (node (ref "B16") (pin "2") (pinfunction "SW2_2") (pintype "bidirectional"))
      (node (ref "IC4") (pin "8") (pinfunction "GPB7_8") (pintype "bidirectional"))
    )
    (net (code "29") (name "I2C_SCL") (class "Default")
      (node (ref "IC2") (pin "12") (pinfunction "SCL_12") (pintype "input"))
      (node (ref "IC3") (pin "26") (pinfunction "SCL_26") (pintype "input"))
      (node (ref "IC4") (pin "12") (pinfunction "SCL_12") (pintype "input"))
      (node (ref "JP4") (pin "2") (pinfunction "2_2") (pintype "passive"))
      (node (ref "R2") (pin "1") (pinfunction "1_1") (pintype "passive"))
    )
    (net (code "30") (name "I2C_SDA") (class "Default")
      (node (ref "IC2") (pin "13") (pinfunction "SDA_13") (pintype "bidirectional"))
      (node (ref "IC3") (pin "27") (pinfunction "SDA_27") (pintype "input"))
      (node (ref "IC4") (pin "13") (pinfunction "SDA_13") (pintype "bidirectional"))
      (node (ref "JP4") (pin "1") (pinfunction "1_1") (pintype "passive"))
      (node (ref "R1") (pin "1") (pinfunction "1_1") (pintype "passive"))
    )
    (net (code "31") (name "IRIS_CONTROL") (class "Default")
      (node (ref "C18") (pin "1") (pinfunction "1_1") (pintype "passive"))
      (node (ref "IC5") (pin "1") (pinfunction "OUT_1") (pintype "output"))
      (node (ref "JP2") (pin "5") (pinfunction "5_5") (pintype "passive"))
      (node (ref "R9") (pin "1") (pinfunction "1_1") (pintype "passive"))
    )
    (net (code "32") (name "L0") (class "Default")
      (node (ref "B1") (pin "L1") (pinfunction "L1_L1") (pintype "bidirectional"))
      (node (ref "B1") (pin "L2") (pinfunction "L2_L2") (pintype "bidirectional"))
      (node (ref "R37") (pin "1") (pinfunction "1_1") (pintype "passive"))
    )
    (net (code "33") (name "L1") (class "Default")
      (node (ref "B2") (pin "L1") (pinfunction "L1_L1") (pintype "bidirectional"))
      (node (ref "B2") (pin "L2") (pinfunction "L2_L2") (pintype "bidirectional"))
      (node (ref "R36") (pin "1") (pinfunction "1_1") (pintype "passive"))
    )
    (net (code "34") (name "L2") (class "Default")
      (node (ref "B3") (pin "L1") (pinfunction "L1_L1") (pintype "bidirectional"))
      (node (ref "B3") (pin "L2") (pinfunction "L2_L2") (pintype "bidirectional"))
      (node (ref "R35") (pin "1") (pinfunction "1_1") (pintype "passive"))
    )
    (net (code "35") (name "L3") (class "Default")
      (node (ref "B4") (pin "L1") (pinfunction "L1_L1") (pintype "bidirectional"))
      (node (ref "B4") (pin "L2") (pinfunction "L2_L2") (pintype "bidirectional"))
      (node (ref "R34") (pin "1") (pinfunction "1_1") (pintype "passive"))
    )
    (net (code "36") (name "L4") (class "Default")
      (node (ref "B5") (pin "L1") (pinfunction "L1_L1") (pintype "bidirectional"))
      (node (ref "B5") (pin "L2") (pinfunction "L2_L2") (pintype "bidirectional"))
      (node (ref "R33") (pin "1") (pinfunction "1_1") (pintype "passive"))
    )
    (net (code "37") (name "L5") (class "Default")
      (node (ref "B6") (pin "L1") (pinfunction "L1_L1") (pintype "bidirectional"))
      (node (ref "B6") (pin "L2") (pinfunction "L2_L2") (pintype "bidirectional"))
      (node (ref "R32") (pin "1") (pinfunction "1_1") (pintype "passive"))
    )
    (net (code "38") (name "L6") (class "Default")
      (node (ref "B7") (pin "L1") (pinfunction "L1_L1") (pintype "bidirectional"))
      (node (ref "B7") (pin "L2") (pinfunction "L2_L2") (pintype "bidirectional"))
      (node (ref "R31") (pin "1") (pinfunction "1_1") (pintype "passive"))
    )
    (net (code "39") (name "L7") (class "Default")
      (node (ref "B8") (pin "L1") (pinfunction "L1_L1") (pintype "bidirectional"))
      (node (ref "B8") (pin "L2") (pinfunction "L2_L2") (pintype "bidirectional"))
      (node (ref "R30") (pin "1") (pinfunction "1_1") (pintype "passive"))
    )
    (net (code "40") (name "L8") (class "Default")
      (node (ref "B9") (pin "L1") (pinfunction "L1_L1") (pintype "bidirectional"))
      (node (ref "B9") (pin "L2") (pinfunction "L2_L2") (pintype "bidirectional"))
      (node (ref "R29") (pin "1") (pinfunction "1_1") (pintype "passive"))
    )
    (net (code "41") (name "L9") (class "Default")
      (node (ref "B10") (pin "L1") (pinfunction "L1_L1") (pintype "bidirectional"))
      (node (ref "B10") (pin "L2") (pinfunction "L2_L2") (pintype "bidirectional"))
      (node (ref "R28") (pin "1") (pinfunction "1_1") (pintype "passive"))
    )
    (net (code "42") (name "L10") (class "Default")
      (node (ref "B11") (pin "L1") (pinfunction "L1_L1") (pintype "bidirectional"))
      (node (ref "B11") (pin "L2") (pinfunction "L2_L2") (pintype "bidirectional"))
      (node (ref "R27") (pin "1") (pinfunction "1_1") (pintype "passive"))
    )
    (net (code "43") (name "L11") (class "Default")
      (node (ref "B12") (pin "L1") (pinfunction "L1_L1") (pintype "bidirectional"))
      (node (ref "B12") (pin "L2") (pinfunction "L2_L2") (pintype "bidirectional"))
      (node (ref "R26") (pin "1") (pinfunction "1_1") (pintype "passive"))
    )
    (net (code "44") (name "L12") (class "Default")
      (node (ref "B13") (pin "L1") (pinfunction "L1_L1") (pintype "bidirectional"))
      (node (ref "B13") (pin "L2") (pinfunction "L2_L2") (pintype "bidirectional"))
      (node (ref "R25") (pin "1") (pinfunction "1_1") (pintype "passive"))
    )
    (net (code "45") (name "L13") (class "Default")
      (node (ref "B14") (pin "L1") (pinfunction "L1_L1") (pintype "bidirectional"))
      (node (ref "B14") (pin "L2") (pinfunction "L2_L2") (pintype "bidirectional"))
      (node (ref "R24") (pin "1") (pinfunction "1_1") (pintype "passive"))
    )
    (net (code "46") (name "L14") (class "Default")
      (node (ref "B15") (pin "L1") (pinfunction "L1_L1") (pintype "bidirectional"))
      (node (ref "B15") (pin "L2") (pinfunction "L2_L2") (pintype "bidirectional"))
      (node (ref "R23") (pin "1") (pinfunction "1_1") (pintype "passive"))
    )
    (net (code "47") (name "L15") (class "Default")
      (node (ref "B16") (pin "L1") (pinfunction "L1_L1") (pintype "bidirectional"))
      (node (ref "B16") (pin "L2") (pinfunction "L2_L2") (pintype "bidirectional"))
      (node (ref "R22") (pin "1") (pinfunction "1_1") (pintype "passive"))
    )
    (net (code "48") (name "Net-(C17-Pad1)") (class "Default")
      (node (ref "C17") (pin "1") (pinfunction "1_1") (pintype "passive"))
      (node (ref "R11") (pin "1") (pinfunction "1_1") (pintype "passive"))
      (node (ref "R12") (pin "2") (pinfunction "2_2") (pintype "passive"))
    )
    (net (code "49") (name "Net-(D7-A)") (class "Default")
      (node (ref "D7") (pin "2") (pinfunction "A_2") (pintype "passive"))
      (node (ref "IO2") (pin "1") (pinfunction "1_1") (pintype "passive"))
      (node (ref "OK1") (pin "4") (pinfunction "C_4") (pintype "passive"))
    )
    (net (code "50") (name "Net-(D7-C)") (class "Default")
      (node (ref "D7") (pin "1") (pinfunction "C_1") (pintype "passive"))
      (node (ref "OK1") (pin "3") (pinfunction "A_3") (pintype "passive"))
      (node (ref "R13") (pin "2") (pinfunction "2_2") (pintype "passive"))
    )
    (net (code "51") (name "Net-(D8-A)") (class "Default")
      (node (ref "D8") (pin "2") (pinfunction "A_2") (pintype "passive"))
      (node (ref "IO1") (pin "1") (pinfunction "1_1") (pintype "passive"))
      (node (ref "OK1") (pin "2") (pinfunction "C_2") (pintype "passive"))
    )
    (net (code "52") (name "Net-(D8-C)") (class "Default")
      (node (ref "D8") (pin "1") (pinfunction "C_1") (pintype "passive"))
      (node (ref "OK1") (pin "1") (pinfunction "A_1") (pintype "passive"))
      (node (ref "R14") (pin "2") (pinfunction "2_2") (pintype "passive"))
    )
    (net (code "53") (name "Net-(GND-Pad5V)") (class "Default")
      (node (ref "GND") (pin "5V") (pinfunction "5V_5V") (pintype "bidirectional"))
      (node (ref "L4") (pin "1") (pinfunction "1_1") (pintype "passive"))
      (node (ref "PC2") (pin "+") (pinfunction "+_+") (pintype "passive"))
    )
    (net (code "54") (name "Net-(IC1-I1)") (class "Default")
      (node (ref "IC1") (pin "1") (pinfunction "I1_1") (pintype "input"))
      (node (ref "IC2") (pin "1") (pinfunction "GPB0_1") (pintype "bidirectional"))
    )
    (net (code "55") (name "Net-(IC1-I2)") (class "Default")
      (node (ref "IC1") (pin "2") (pinfunction "I2_2") (pintype "input"))
      (node (ref "IC2") (pin "2") (pinfunction "GPB1_2") (pintype "bidirectional"))
    )
    (net (code "56") (name "Net-(IC1-I3)") (class "Default")
      (node (ref "IC1") (pin "3") (pinfunction "I3_3") (pintype "input"))
      (node (ref "IC2") (pin "3") (pinfunction "GPB2_3") (pintype "bidirectional"))
    )
    (net (code "57") (name "Net-(IC1-I4)") (class "Default")
      (node (ref "IC1") (pin "4") (pinfunction "I4_4") (pintype "input"))
      (node (ref "IC2") (pin "4") (pinfunction "GPB3_4") (pintype "bidirectional"))
    )
    (net (code "58") (name "Net-(IC1-I5)") (class "Default")
      (node (ref "IC1") (pin "5") (pinfunction "I5_5") (pintype "input"))
      (node (ref "IC2") (pin "5") (pinfunction "GPB4_5") (pintype "bidirectional"))
    )
    (net (code "59") (name "Net-(IC1-I6)") (class "Default")
      (node (ref "IC1") (pin "6") (pinfunction "I6_6") (pintype "input"))
      (node (ref "IC2") (pin "6") (pinfunction "GPB5_6") (pintype "bidirectional"))
    )
    (net (code "60") (name "Net-(IC1-I7)") (class "Default")
      (node (ref "IC1") (pin "7") (pinfunction "I7_7") (pintype "input"))
      (node (ref "IC2") (pin "7") (pinfunction "GPB6_7") (pintype "bidirectional"))
    )
    (net (code "61") (name "Net-(IC1-I8)") (class "Default")
      (node (ref "IC1") (pin "8") (pinfunction "I8_8") (pintype "input"))
      (node (ref "IC2") (pin "8") (pinfunction "GPB7_8") (pintype "bidirectional"))
    )
    (net (code "62") (name "Net-(IC1-O1)") (class "Default")
      (node (ref "IC1") (pin "18") (pinfunction "O1_18") (pintype "open_collector"))
      (node (ref "K1") (pin "16") (pinfunction "2_16") (pintype "passive"))
    )
    (net (code "63") (name "Net-(IC1-O2)") (class "Default")
      (node (ref "IC1") (pin "17") (pinfunction "O2_17") (pintype "open_collector"))
      (node (ref "K2") (pin "16") (pinfunction "2_16") (pintype "passive"))
    )
    (net (code "64") (name "Net-(IC2-GPA0)") (class "Default")
      (node (ref "IC2") (pin "21") (pinfunction "GPA0_21") (pintype "bidirectional"))
      (node (ref "OK1") (pin "8") (pinfunction "COL_8") (pintype "passive"))
    )
    (net (code "65") (name "Net-(IC2-GPA1)") (class "Default")
      (node (ref "IC2") (pin "22") (pinfunction "GPA1_22") (pintype "bidirectional"))
      (node (ref "OK1") (pin "6") (pinfunction "COL_6") (pintype "passive"))
    )
    (net (code "66") (name "Net-(IC3-L0)") (class "Default")
      (node (ref "IC3") (pin "6") (pinfunction "L0_6") (pintype "output"))
      (node (ref "R37") (pin "2") (pinfunction "2_2") (pintype "passive"))
    )
    (net (code "67") (name "Net-(IC3-L1)") (class "Default")
      (node (ref "IC3") (pin "7") (pinfunction "L1_7") (pintype "output"))
      (node (ref "R36") (pin "2") (pinfunction "2_2") (pintype "passive"))
    )
    (net (code "68") (name "Net-(IC3-L2)") (class "Default")
      (node (ref "IC3") (pin "8") (pinfunction "L2_8") (pintype "output"))
      (node (ref "R35") (pin "2") (pinfunction "2_2") (pintype "passive"))
    )
    (net (code "69") (name "Net-(IC3-L3)") (class "Default")
      (node (ref "IC3") (pin "9") (pinfunction "L3_9") (pintype "output"))
      (node (ref "R34") (pin "2") (pinfunction "2_2") (pintype "passive"))
    )
    (net (code "70") (name "Net-(IC3-L4)") (class "Default")
      (node (ref "IC3") (pin "10") (pinfunction "L4_10") (pintype "output"))
      (node (ref "R33") (pin "2") (pinfunction "2_2") (pintype "passive"))
    )
    (net (code "71") (name "Net-(IC3-L5)") (class "Default")
      (node (ref "IC3") (pin "11") (pinfunction "L5_11") (pintype "output"))
      (node (ref "R32") (pin "2") (pinfunction "2_2") (pintype "passive"))
    )
    (net (code "72") (name "Net-(IC3-L6)") (class "Default")
      (node (ref "IC3") (pin "12") (pinfunction "L6_12") (pintype "output"))
      (node (ref "R31") (pin "2") (pinfunction "2_2") (pintype "passive"))
    )
    (net (code "73") (name "Net-(IC3-L7)") (class "Default")
      (node (ref "IC3") (pin "13") (pinfunction "L7_13") (pintype "output"))
      (node (ref "R30") (pin "2") (pinfunction "2_2") (pintype "passive"))
    )
    (net (code "74") (name "Net-(IC3-L8)") (class "Default")
      (node (ref "IC3") (pin "15") (pinfunction "L8_15") (pintype "output"))
      (node (ref "R29") (pin "2") (pinfunction "2_2") (pintype "passive"))
    )
    (net (code "75") (name "Net-(IC3-L9)") (class "Default")
      (node (ref "IC3") (pin "16") (pinfunction "L9_16") (pintype "output"))
      (node (ref "R28") (pin "2") (pinfunction "2_2") (pintype "passive"))
    )
    (net (code "76") (name "Net-(IC3-L10)") (class "Default")
      (node (ref "IC3") (pin "17") (pinfunction "L10_17") (pintype "output"))
      (node (ref "R27") (pin "2") (pinfunction "2_2") (pintype "passive"))
    )
    (net (code "77") (name "Net-(IC3-L11)") (class "Default")
      (node (ref "IC3") (pin "18") (pinfunction "L11_18") (pintype "output"))
      (node (ref "R26") (pin "2") (pinfunction "2_2") (pintype "passive"))
    )
    (net (code "78") (name "Net-(IC3-L12)") (class "Default")
      (node (ref "IC3") (pin "19") (pinfunction "L12_19") (pintype "output"))
      (node (ref "R25") (pin "2") (pinfunction "2_2") (pintype "passive"))
    )
    (net (code "79") (name "Net-(IC3-L13)") (class "Default")
      (node (ref "IC3") (pin "20") (pinfunction "L13_20") (pintype "output"))
      (node (ref "R24") (pin "2") (pinfunction "2_2") (pintype "passive"))
    )
    (net (code "80") (name "Net-(IC3-L14)") (class "Default")
      (node (ref "IC3") (pin "21") (pinfunction "L14_21") (pintype "output"))
      (node (ref "R23") (pin "2") (pinfunction "2_2") (pintype "passive"))
    )
    (net (code "81") (name "Net-(IC3-L15)") (class "Default")
      (node (ref "IC3") (pin "22") (pinfunction "L15_22") (pintype "output"))
      (node (ref "R22") (pin "2") (pinfunction "2_2") (pintype "passive"))
    )
    (net (code "82") (name "Net-(IC5A-+IN)") (class "Default")
      (node (ref "C16") (pin "1") (pinfunction "1_1") (pintype "passive"))
      (node (ref "IC5") (pin "3") (pinfunction "+IN_3") (pintype "input"))
      (node (ref "R12") (pin "1") (pinfunction "1_1") (pintype "passive"))
    )
    (net (code "83") (name "Net-(IC5A--IN)") (class "Default")
      (node (ref "IC5") (pin "2") (pinfunction "-IN_2") (pintype "input"))
      (node (ref "R10") (pin "1") (pinfunction "1_1") (pintype "passive"))
      (node (ref "R9") (pin "2") (pinfunction "2_2") (pintype "passive"))
    )
    (net (code "84") (name "Net-(JP2-Pad7)") (class "Default")
      (node (ref "JP2") (pin "7") (pinfunction "7_7") (pintype "passive"))
      (node (ref "R6") (pin "2") (pinfunction "2_2") (pintype "passive"))
    )
    (net (code "85") (name "Net-(JP3-Pad4)") (class "Default")
      (node (ref "JP3") (pin "4") (pinfunction "4_4") (pintype "passive"))
      (node (ref "JP5") (pin "4") (pinfunction "4_4") (pintype "passive"))
    )
    (net (code "86") (name "Net-(JP3-Pad5)") (class "Default")
      (node (ref "JP3") (pin "5") (pinfunction "5_5") (pintype "passive"))
      (node (ref "JP5") (pin "5") (pinfunction "5_5") (pintype "passive"))
    )
    (net (code "87") (name "Net-(JP3-Pad6)") (class "Default")
      (node (ref "JP3") (pin "6") (pinfunction "6_6") (pintype "passive"))
      (node (ref "JP5") (pin "6") (pinfunction "6_6") (pintype "passive"))
    )
    (net (code "88") (name "Net-(K1B-S)") (class "Default")
      (node (ref "IO1") (pin "3") (pinfunction "3_3") (pintype "passive"))
      (node (ref "K1") (pin "S1") (pinfunction "S_S1") (pintype "passive"))
    )
    (net (code "89") (name "Net-(K2B-S)") (class "Default")
      (node (ref "IO2") (pin "3") (pinfunction "3_3") (pintype "passive"))
      (node (ref "K2") (pin "S1") (pinfunction "S_S1") (pintype "passive"))
    )
    (net (code "90") (name "Net-(S3-O)") (class "Default")
      (node (ref "R8") (pin "1") (pinfunction "1_1") (pintype "passive"))
      (node (ref "S3") (pin "P$1") (pinfunction "O_P$1") (pintype "passive"))
    )
    (net (code "91") (name "Net-(S3-S)") (class "Default")
      (node (ref "JP2") (pin "4") (pinfunction "4_4") (pintype "passive"))
      (node (ref "R5") (pin "1") (pinfunction "1_1") (pintype "passive"))
      (node (ref "S3") (pin "P$3") (pinfunction "S_P$3") (pintype "passive"))
    )
    (net (code "92") (name "Net-(T6-B)") (class "Default")
      (node (ref "R39") (pin "1") (pinfunction "1_1") (pintype "passive"))
      (node (ref "T6") (pin "1") (pinfunction "B_1") (pintype "passive"))
    )
    (net (code "93") (name "Net-(T6-C)") (class "Default")
      (node (ref "T6") (pin "3") (pinfunction "C_3") (pintype "passive"))
      (node (ref "X6") (pin "3") (pinfunction "1_3") (pintype "passive"))
    )
    (net (code "94") (name "Net-(U$7-P$2)") (class "Default")
      (node (ref "R4") (pin "1") (pinfunction "1_1") (pintype "passive"))
      (node (ref "U$7") (pin "A2") (pinfunction "P$2_A2") (pintype "bidirectional"))
    )
    (net (code "95") (name "Net-(U$7-P$3)") (class "Default")
      (node (ref "R3") (pin "1") (pinfunction "1_1") (pintype "passive"))
      (node (ref "U$7") (pin "A3") (pinfunction "P$3_A3") (pintype "bidirectional"))
    )
    (net (code "96") (name "Net-(U$12-C)") (class "Default")
      (node (ref "R8") (pin "2") (pinfunction "2_2") (pintype "passive"))
      (node (ref "U$12") (pin "K") (pinfunction "C_K") (pintype "passive"))
    )
    (net (code "97") (name "Net-(X6B-1)") (class "Default")
      (node (ref "C3") (pin "1") (pinfunction "1_1") (pintype "passive"))
      (node (ref "JP2") (pin "6") (pinfunction "6_6") (pintype "passive"))
      (node (ref "L1") (pin "1") (pinfunction "1_1") (pintype "passive"))
      (node (ref "PC1") (pin "+") (pinfunction "+_+") (pintype "passive"))
      (node (ref "X6") (pin "2") (pinfunction "1_2") (pintype "passive"))
    )
    (net (code "98") (name "Net-(X6D-1)") (class "Default")
      (node (ref "IO1") (pin "2") (pinfunction "2_2") (pintype "passive"))
      (node (ref "X6") (pin "4") (pinfunction "1_4") (pintype "passive"))
    )
    (net (code "99") (name "Net-(X6E-1)") (class "Default")
      (node (ref "IO2") (pin "2") (pinfunction "2_2") (pintype "passive"))
      (node (ref "X6") (pin "5") (pinfunction "1_5") (pintype "passive"))
    )
    (net (code "100") (name "PRV_TALLY") (class "Default")
      (node (ref "GND") (pin "D4") (pinfunction "D4_D4") (pintype "bidirectional"))
      (node (ref "R39") (pin "2") (pinfunction "2_2") (pintype "passive"))
    )
    (net (code "101") (name "PWM_IRIS") (class "Default")
      (node (ref "GND") (pin "D5") (pinfunction "*D5_D5") (pintype "bidirectional"))
      (node (ref "R11") (pin "2") (pinfunction "2_2") (pintype "passive"))
    )
    (net (code "102") (name "RES") (class "Default")
      (node (ref "GND") (pin "RES") (pinfunction "RES_RES") (pintype "bidirectional"))
      (node (ref "RESET") (pin "1") (pinfunction "1_1") (pintype "passive"))
      (node (ref "RESETA") (pin "1") (pinfunction "1_1") (pintype "passive"))
    )
    (net (code "103") (name "VIN") (class "Default")
      (node (ref "C15") (pin "1") (pinfunction "1_1") (pintype "passive"))
      (node (ref "C7") (pin "1") (pinfunction "1_1") (pintype "passive"))
      (node (ref "C9") (pin "1") (pinfunction "1_1") (pintype "passive"))
      (node (ref "GND") (pin "VIN") (pinfunction "VIN_VIN") (pintype "bidirectional"))
      (node (ref "IC5") (pin "8") (pinfunction "V+_8") (pintype "power_in"))
      (node (ref "L1") (pin "2") (pinfunction "2_2") (pintype "passive"))
    )
    (net (code "104") (name "unconnected-(B1-PadL3)") (class "Default")
      (node (ref "B1") (pin "L3") (pinfunction "L3_L3") (pintype "bidirectional"))
    )
    (net (code "105") (name "unconnected-(B1-PadL4)") (class "Default")
      (node (ref "B1") (pin "L4") (pinfunction "L4_L4") (pintype "bidirectional"))
    )
    (net (code "106") (name "unconnected-(B1-PadLC2)") (class "Default")
      (node (ref "B1") (pin "LC2") (pinfunction "LC2_LC2") (pintype "bidirectional"))
    )
    (net (code "107") (name "unconnected-(B2-PadL3)") (class "Default")
      (node (ref "B2") (pin "L3") (pinfunction "L3_L3") (pintype "bidirectional"))
    )
    (net (code "108") (name "unconnected-(B2-PadL4)") (class "Default")
      (node (ref "B2") (pin "L4") (pinfunction "L4_L4") (pintype "bidirectional"))
    )
    (net (code "109") (name "unconnected-(B2-PadLC2)") (class "Default")
      (node (ref "B2") (pin "LC2") (pinfunction "LC2_LC2") (pintype "bidirectional"))
    )
    (net (code "110") (name "unconnected-(B3-PadL3)") (class "Default")
      (node (ref "B3") (pin "L3") (pinfunction "L3_L3") (pintype "bidirectional"))
    )
    (net (code "111") (name "unconnected-(B3-PadL4)") (class "Default")
      (node (ref "B3") (pin "L4") (pinfunction "L4_L4") (pintype "bidirectional"))
    )
    (net (code "112") (name "unconnected-(B3-PadLC2)") (class "Default")
      (node (ref "B3") (pin "LC2") (pinfunction "LC2_LC2") (pintype "bidirectional"))
    )
    (net (code "113") (name "unconnected-(B4-PadL3)") (class "Default")
      (node (ref "B4") (pin "L3") (pinfunction "L3_L3") (pintype "bidirectional"))
    )
    (net (code "114") (name "unconnected-(B4-PadL4)") (class "Default")
      (node (ref "B4") (pin "L4") (pinfunction "L4_L4") (pintype "bidirectional"))
    )
    (net (code "115") (name "unconnected-(B4-PadLC2)") (class "Default")
      (node (ref "B4") (pin "LC2") (pinfunction "LC2_LC2") (pintype "bidirectional"))
    )
    (net (code "116") (name "unconnected-(B5-PadL3)") (class "Default")
      (node (ref "B5") (pin "L3") (pinfunction "L3_L3") (pintype "bidirectional"))
    )
    (net (code "117") (name "unconnected-(B5-PadL4)") (class "Default")
      (node (ref "B5") (pin "L4") (pinfunction "L4_L4") (pintype "bidirectional"))
    )
    (net (code "118") (name "unconnected-(B5-PadLC2)") (class "Default")
      (node (ref "B5") (pin "LC2") (pinfunction "LC2_LC2") (pintype "bidirectional"))
    )
    (net (code "119") (name "unconnected-(B6-PadL3)") (class "Default")
      (node (ref "B6") (pin "L3") (pinfunction "L3_L3") (pintype "bidirectional"))
    )
    (net (code "120") (name "unconnected-(B6-PadL4)") (class "Default")
      (node (ref "B6") (pin "L4") (pinfunction "L4_L4") (pintype "bidirectional"))
    )
    (net (code "121") (name "unconnected-(B6-PadLC2)") (class "Default")
      (node (ref "B6") (pin "LC2") (pinfunction "LC2_LC2") (pintype "bidirectional"))
    )
    (net (code "122") (name "unconnected-(B7-PadL3)") (class "Default")
      (node (ref "B7") (pin "L3") (pinfunction "L3_L3") (pintype "bidirectional"))
    )
    (net (code "123") (name "unconnected-(B7-PadL4)") (class "Default")
      (node (ref "B7") (pin "L4") (pinfunction "L4_L4") (pintype "bidirectional"))
    )
    (net (code "124") (name "unconnected-(B7-PadLC2)") (class "Default")
      (node (ref "B7") (pin "LC2") (pinfunction "LC2_LC2") (pintype "bidirectional"))
    )
    (net (code "125") (name "unconnected-(B8-PadL3)") (class "Default")
      (node (ref "B8") (pin "L3") (pinfunction "L3_L3") (pintype "bidirectional"))
    )
    (net (code "126") (name "unconnected-(B8-PadL4)") (class "Default")
      (node (ref "B8") (pin "L4") (pinfunction "L4_L4") (pintype "bidirectional"))
    )
    (net (code "127") (name "unconnected-(B8-PadLC2)") (class "Default")
      (node (ref "B8") (pin "LC2") (pinfunction "LC2_LC2") (pintype "bidirectional"))
    )
    (net (code "128") (name "unconnected-(B9-PadL3)") (class "Default")
      (node (ref "B9") (pin "L3") (pinfunction "L3_L3") (pintype "bidirectional"))
    )
    (net (code "129") (name "unconnected-(B9-PadL4)") (class "Default")
      (node (ref "B9") (pin "L4") (pinfunction "L4_L4") (pintype "bidirectional"))
    )
    (net (code "130") (name "unconnected-(B9-PadLC2)") (class "Default")
      (node (ref "B9") (pin "LC2") (pinfunction "LC2_LC2") (pintype "bidirectional"))
    )
    (net (code "131") (name "unconnected-(B10-PadL3)") (class "Default")
      (node (ref "B10") (pin "L3") (pinfunction "L3_L3") (pintype "bidirectional"))
    )
    (net (code "132") (name "unconnected-(B10-PadL4)") (class "Default")
      (node (ref "B10") (pin "L4") (pinfunction "L4_L4") (pintype "bidirectional"))
    )
    (net (code "133") (name "unconnected-(B10-PadLC2)") (class "Default")
      (node (ref "B10") (pin "LC2") (pinfunction "LC2_LC2") (pintype "bidirectional"))
    )
    (net (code "134") (name "unconnected-(B11-PadL3)") (class "Default")
      (node (ref "B11") (pin "L3") (pinfunction "L3_L3") (pintype "bidirectional"))
    )
    (net (code "135") (name "unconnected-(B11-PadL4)") (class "Default")
      (node (ref "B11") (pin "L4") (pinfunction "L4_L4") (pintype "bidirectional"))
    )
    (net (code "136") (name "unconnected-(B11-PadLC2)") (class "Default")
      (node (ref "B11") (pin "LC2") (pinfunction "LC2_LC2") (pintype "bidirectional"))
    )
    (net (code "137") (name "unconnected-(B12-PadL3)") (class "Default")
      (node (ref "B12") (pin "L3") (pinfunction "L3_L3") (pintype "bidirectional"))
    )
    (net (code "138") (name "unconnected-(B12-PadL4)") (class "Default")
      (node (ref "B12") (pin "L4") (pinfunction "L4_L4") (pintype "bidirectional"))
    )
    (net (code "139") (name "unconnected-(B12-PadLC2)") (class "Default")
      (node (ref "B12") (pin "LC2") (pinfunction "LC2_LC2") (pintype "bidirectional"))
    )
    (net (code "140") (name "unconnected-(B13-PadL3)") (class "Default")
      (node (ref "B13") (pin "L3") (pinfunction "L3_L3") (pintype "bidirectional"))
    )
    (net (code "141") (name "unconnected-(B13-PadL4)") (class "Default")
      (node (ref "B13") (pin "L4") (pinfunction "L4_L4") (pintype "bidirectional"))
    )
    (net (code "142") (name "unconnected-(B13-PadLC2)") (class "Default")
      (node (ref "B13") (pin "LC2") (pinfunction "LC2_LC2") (pintype "bidirectional"))
    )
    (net (code "143") (name "unconnected-(B14-PadL3)") (class "Default")
      (node (ref "B14") (pin "L3") (pinfunction "L3_L3") (pintype "bidirectional"))
    )
    (net (code "144") (name "unconnected-(B14-PadL4)") (class "Default")
      (node (ref "B14") (pin "L4") (pinfunction "L4_L4") (pintype "bidirectional"))
    )
    (net (code "145") (name "unconnected-(B14-PadLC2)") (class "Default")
      (node (ref "B14") (pin "LC2") (pinfunction "LC2_LC2") (pintype "bidirectional"))
    )
    (net (code "146") (name "unconnected-(B15-PadL3)") (class "Default")
      (node (ref "B15") (pin "L3") (pinfunction "L3_L3") (pintype "bidirectional"))
    )
    (net (code "147") (name "unconnected-(B15-PadL4)") (class "Default")
      (node (ref "B15") (pin "L4") (pinfunction "L4_L4") (pintype "bidirectional"))
    )
    (net (code "148") (name "unconnected-(B15-PadLC2)") (class "Default")
      (node (ref "B15") (pin "LC2") (pinfunction "LC2_LC2") (pintype "bidirectional"))
    )
    (net (code "149") (name "unconnected-(B16-PadL3)") (class "Default")
      (node (ref "B16") (pin "L3") (pinfunction "L3_L3") (pintype "bidirectional"))
    )
    (net (code "150") (name "unconnected-(B16-PadL4)") (class "Default")
      (node (ref "B16") (pin "L4") (pinfunction "L4_L4") (pintype "bidirectional"))
    )
    (net (code "151") (name "unconnected-(B16-PadLC2)") (class "Default")
      (node (ref "B16") (pin "LC2") (pinfunction "LC2_LC2") (pintype "bidirectional"))
    )
    (net (code "152") (name "unconnected-(GND-*D10-PadD10)") (class "Default")
      (node (ref "GND") (pin "D10") (pinfunction "*D10_D10") (pintype "bidirectional"))
    )
    (net (code "153") (name "unconnected-(GND-*D11-PadD11)") (class "Default")
      (node (ref "GND") (pin "D11") (pinfunction "*D11_D11") (pintype "bidirectional"))
    )
    (net (code "154") (name "unconnected-(GND-Pad3.3V)") (class "Default")
      (node (ref "GND") (pin "3.3V") (pinfunction "3.3V_3.3V") (pintype "bidirectional"))
    )
    (net (code "155") (name "unconnected-(GND-PadA0)") (class "Default")
      (node (ref "GND") (pin "A0") (pinfunction "A0_A0") (pintype "bidirectional"))
    )
    (net (code "156") (name "unconnected-(GND-PadA3)") (class "Default")
      (node (ref "GND") (pin "A3") (pinfunction "A3_A3") (pintype "bidirectional"))
    )
    (net (code "157") (name "unconnected-(GND-PadA4)") (class "Default")
      (node (ref "GND") (pin "A4") (pinfunction "A4_A4") (pintype "bidirectional"))
    )
    (net (code "158") (name "unconnected-(GND-PadA5)") (class "Default")
      (node (ref "GND") (pin "A5") (pinfunction "A5_A5") (pintype "bidirectional"))
    )
    (net (code "159") (name "unconnected-(GND-PadAREF)") (class "Default")
      (node (ref "GND") (pin "AREF") (pinfunction "AREF_AREF") (pintype "bidirectional"))
    )
    (net (code "160") (name "unconnected-(GND-PadD12)") (class "Default")
      (node (ref "GND") (pin "D12") (pinfunction "D12_D12") (pintype "bidirectional"))
    )
    (net (code "161") (name "unconnected-(GND-PadD13)") (class "Default")
      (node (ref "GND") (pin "D13") (pinfunction "D13_D13") (pintype "bidirectional"))
    )
    (net (code "162") (name "unconnected-(GND-PadRX)") (class "Default")
      (node (ref "GND") (pin "RX") (pinfunction "RX_RX") (pintype "bidirectional"))
    )
    (net (code "163") (name "unconnected-(GND-PadTX)") (class "Default")
      (node (ref "GND") (pin "TX") (pinfunction "TX_TX") (pintype "bidirectional"))
    )
    (net (code "164") (name "unconnected-(IC1-O3-Pad16)") (class "Default")
      (node (ref "IC1") (pin "16") (pinfunction "O3_16") (pintype "open_collector"))
    )
    (net (code "165") (name "unconnected-(IC1-O4-Pad15)") (class "Default")
      (node (ref "IC1") (pin "15") (pinfunction "O4_15") (pintype "open_collector"))
    )
    (net (code "166") (name "unconnected-(IC1-O5-Pad14)") (class "Default")
      (node (ref "IC1") (pin "14") (pinfunction "O5_14") (pintype "open_collector"))
    )
    (net (code "167") (name "unconnected-(IC1-O6-Pad13)") (class "Default")
      (node (ref "IC1") (pin "13") (pinfunction "O6_13") (pintype "open_collector"))
    )
    (net (code "168") (name "unconnected-(IC1-O7-Pad12)") (class "Default")
      (node (ref "IC1") (pin "12") (pinfunction "O7_12") (pintype "open_collector"))
    )
    (net (code "169") (name "unconnected-(IC1-O8-Pad11)") (class "Default")
      (node (ref "IC1") (pin "11") (pinfunction "O8_11") (pintype "open_collector"))
    )
    (net (code "170") (name "unconnected-(IC2-GPA2-Pad23)") (class "Default")
      (node (ref "IC2") (pin "23") (pinfunction "GPA2_23") (pintype "bidirectional"))
    )
    (net (code "171") (name "unconnected-(IC2-GPA3-Pad24)") (class "Default")
      (node (ref "IC2") (pin "24") (pinfunction "GPA3_24") (pintype "bidirectional"))
    )
    (net (code "172") (name "unconnected-(IC2-GPA4-Pad25)") (class "Default")
      (node (ref "IC2") (pin "25") (pinfunction "GPA4_25") (pintype "bidirectional"))
    )
    (net (code "173") (name "unconnected-(IC2-GPA5-Pad26)") (class "Default")
      (node (ref "IC2") (pin "26") (pinfunction "GPA5_26") (pintype "bidirectional"))
    )
    (net (code "174") (name "unconnected-(IC2-GPA6-Pad27)") (class "Default")
      (node (ref "IC2") (pin "27") (pinfunction "GPA6_27") (pintype "bidirectional"))
    )
    (net (code "175") (name "unconnected-(IC2-GPA7-Pad28)") (class "Default")
      (node (ref "IC2") (pin "28") (pinfunction "GPA7_28") (pintype "bidirectional"))
    )
    (net (code "176") (name "unconnected-(IC2-INTA-Pad20)") (class "Default")
      (node (ref "IC2") (pin "20") (pinfunction "INTA_20") (pintype "output"))
    )
    (net (code "177") (name "unconnected-(IC2-INTB-Pad19)") (class "Default")
      (node (ref "IC2") (pin "19") (pinfunction "INTB_19") (pintype "output"))
    )
    (net (code "178") (name "unconnected-(IC4-INTA-Pad20)") (class "Default")
      (node (ref "IC4") (pin "20") (pinfunction "INTA_20") (pintype "output"))
    )
    (net (code "179") (name "unconnected-(IC4-INTB-Pad19)") (class "Default")
      (node (ref "IC4") (pin "19") (pinfunction "INTB_19") (pintype "output"))
    )
    (net (code "180") (name "unconnected-(IC5B-+IN-Pad5)") (class "Default")
      (node (ref "IC5") (pin "5") (pinfunction "+IN_5") (pintype "input"))
    )
    (net (code "181") (name "unconnected-(IC5B-OUT-Pad7)") (class "Default")
      (node (ref "IC5") (pin "7") (pinfunction "OUT_7") (pintype "output"))
    )
    (net (code "182") (name "unconnected-(JP1-Pad1)") (class "Default")
      (node (ref "JP1") (pin "1") (pinfunction "1_1") (pintype "passive"))
    )
    (net (code "183") (name "unconnected-(JP1-Pad2)") (class "Default")
      (node (ref "JP1") (pin "2") (pinfunction "2_2") (pintype "passive"))
    )
    (net (code "184") (name "unconnected-(JP2-Pad1)") (class "Default")
      (node (ref "JP2") (pin "1") (pinfunction "1_1") (pintype "passive"))
    )
    (net (code "185") (name "unconnected-(JP2-Pad2)") (class "Default")
      (node (ref "JP2") (pin "2") (pinfunction "2_2") (pintype "passive"))
    )
    (net (code "186") (name "unconnected-(JP2-Pad8)") (class "Default")
      (node (ref "JP2") (pin "8") (pinfunction "8_8") (pintype "passive"))
    )
    (net (code "187") (name "unconnected-(JP2-Pad9)") (class "Default")
      (node (ref "JP2") (pin "9") (pinfunction "9_9") (pintype "passive"))
    )
    (net (code "188") (name "unconnected-(JP2-Pad10)") (class "Default")
      (node (ref "JP2") (pin "10") (pinfunction "10_10") (pintype "passive"))
    )
    (net (code "189") (name "unconnected-(JP3-Pad2)") (class "Default")
      (node (ref "JP3") (pin "2") (pinfunction "2_2") (pintype "passive"))
    )
    (net (code "190") (name "unconnected-(JP3-Pad3)") (class "Default")
      (node (ref "JP3") (pin "3") (pinfunction "3_3") (pintype "passive"))
    )
    (net (code "191") (name "unconnected-(JP5-Pad2)") (class "Default")
      (node (ref "JP5") (pin "2") (pinfunction "2_2") (pintype "passive"))
    )
    (net (code "192") (name "unconnected-(JP5-Pad3)") (class "Default")
      (node (ref "JP5") (pin "3") (pinfunction "3_3") (pintype "passive"))
    )
    (net (code "193") (name "unconnected-(K1B-O-PadO1)") (class "Default")
      (node (ref "K1") (pin "O1") (pinfunction "O_O1") (pintype "passive"))
    )
    (net (code "194") (name "unconnected-(K1C-O-PadO2)") (class "Default")
      (node (ref "K1") (pin "O2") (pinfunction "O_O2") (pintype "passive"))
    )
    (net (code "195") (name "unconnected-(K1C-S-PadS2)") (class "Default")
      (node (ref "K1") (pin "S2") (pinfunction "S_S2") (pintype "passive"))
    )
    (net (code "196") (name "unconnected-(K2B-O-PadO1)") (class "Default")
      (node (ref "K2") (pin "O1") (pinfunction "O_O1") (pintype "passive"))
    )
    (net (code "197") (name "unconnected-(K2C-O-PadO2)") (class "Default")
      (node (ref "K2") (pin "O2") (pinfunction "O_O2") (pintype "passive"))
    )
    (net (code "198") (name "unconnected-(K2C-S-PadS2)") (class "Default")
      (node (ref "K2") (pin "S2") (pinfunction "S_S2") (pintype "passive"))
    )
  )
)
